# Sensor_HallArray_StandAlone_5mm.net
KiCad netlist of a schematic drawn in EAGLE
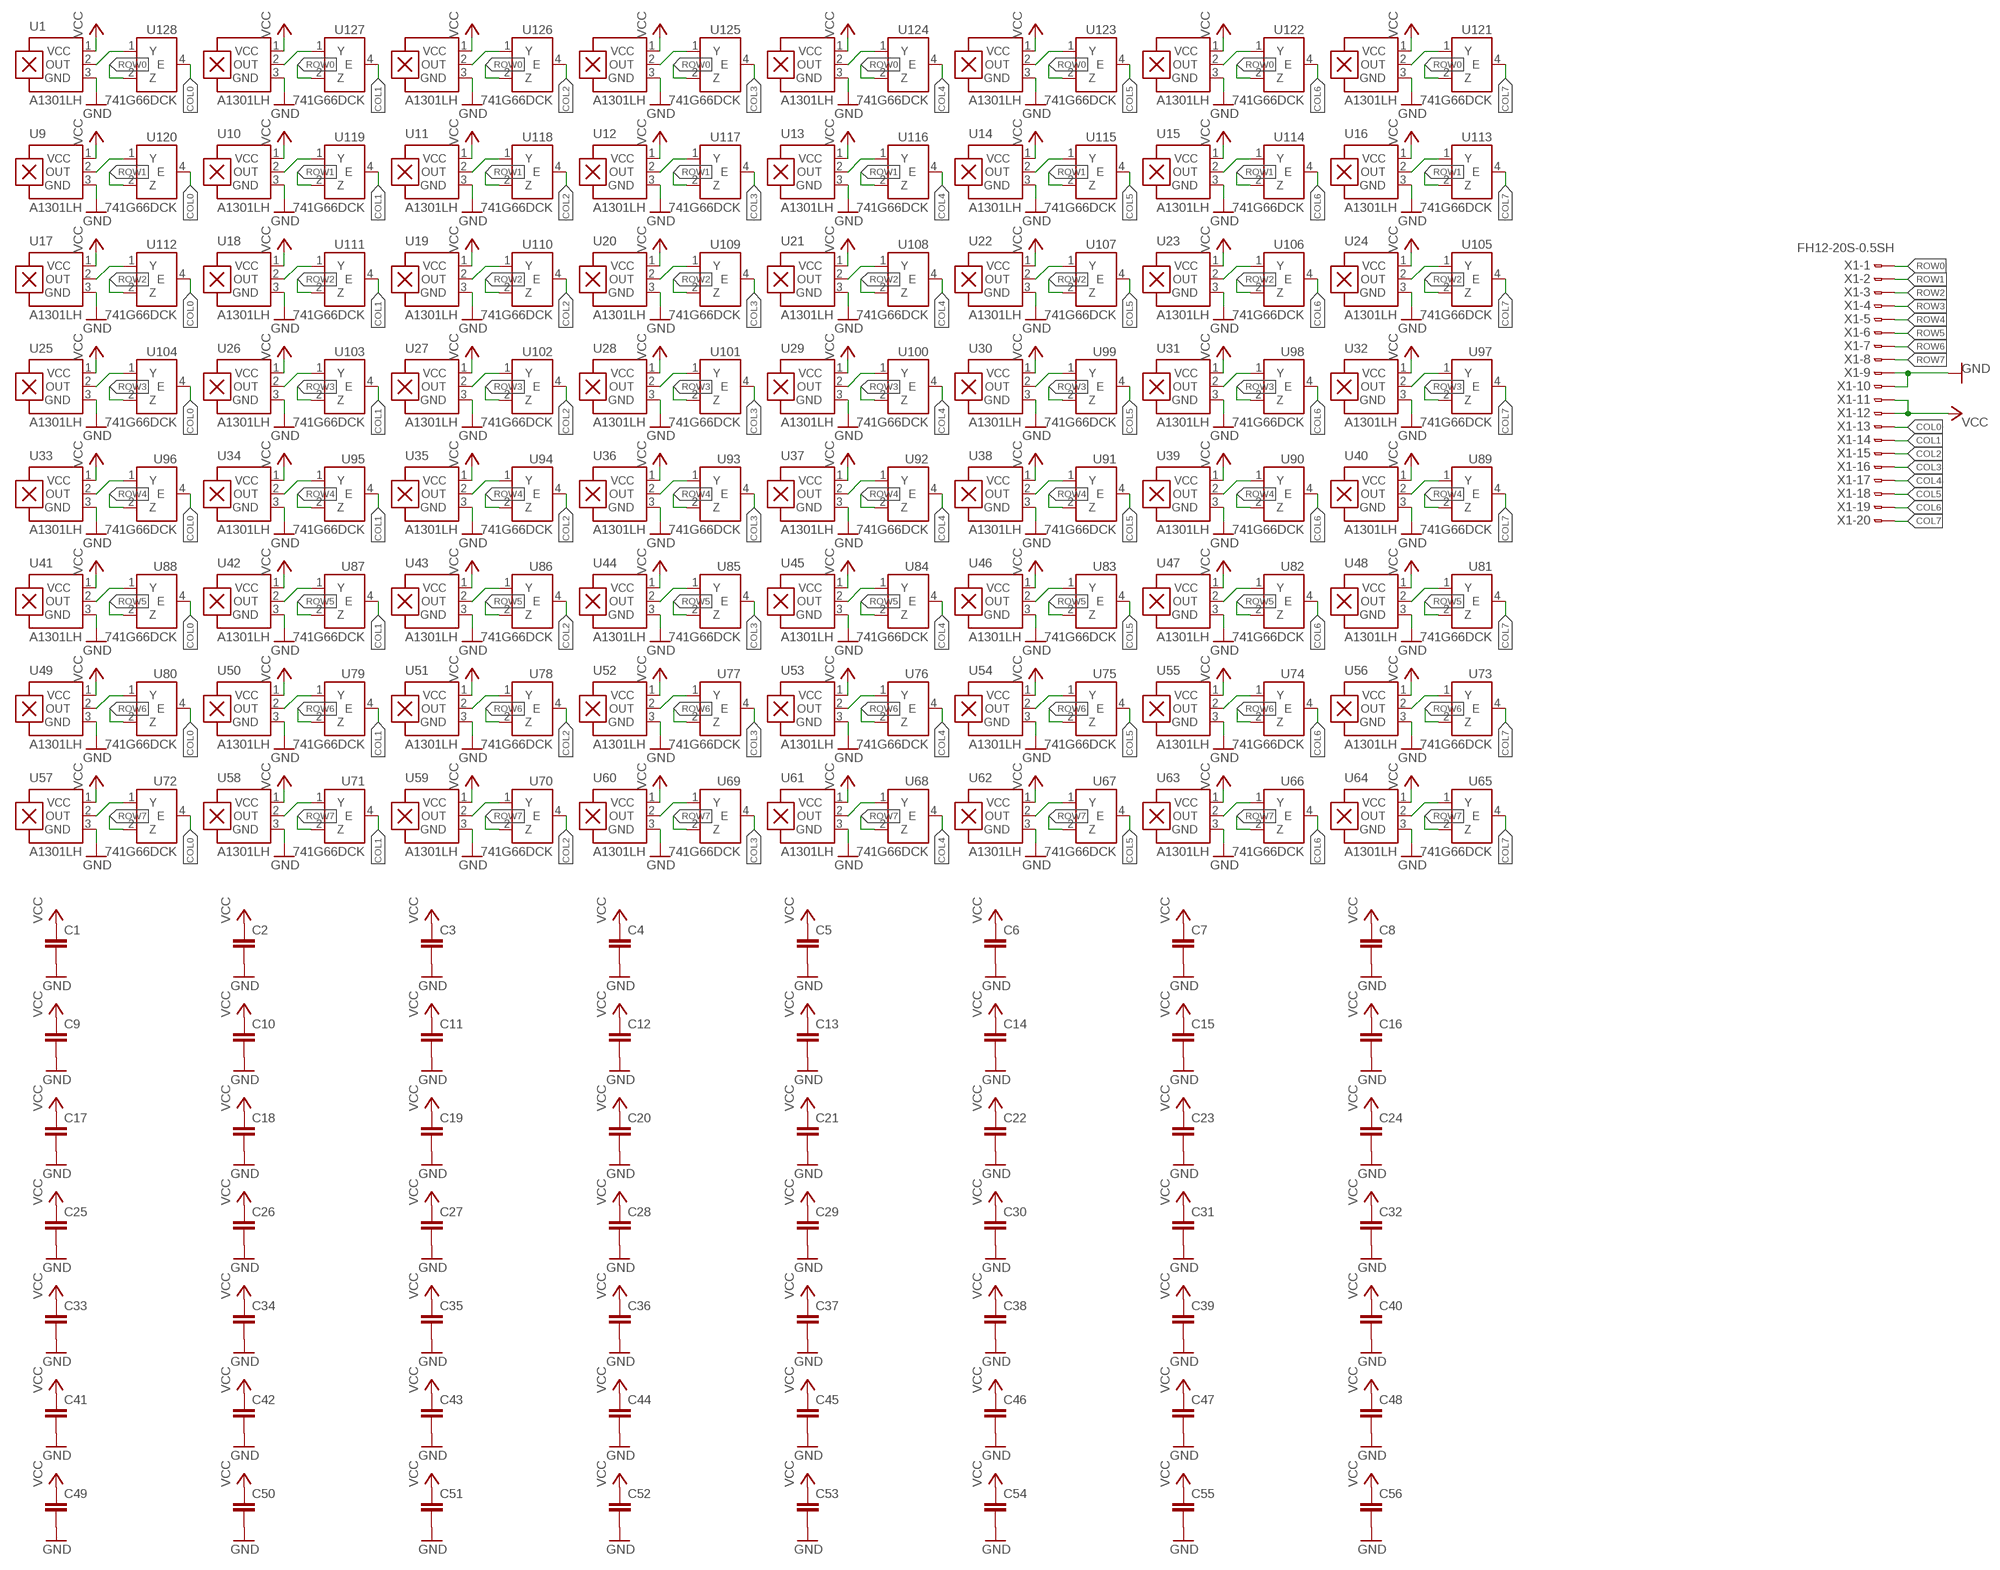
[diagram p0: schematic, sheet 1]

(export (version "E")
  (design (tool "Eeschema 10.0.6"))
  (components
    (comp (ref "C1")
      (value "C-EUC0402")
      (footprint "eagle-import:C0402")
      (libsource (lib "eagle-import") (part "C-EUC0402"))
    )
    (comp (ref "C2")
      (value "C-EUC0402")
      (footprint "eagle-import:C0402")
      (libsource (lib "eagle-import") (part "C-EUC0402"))
    )
    (comp (ref "C3")
      (value "C-EUC0402")
      (footprint "eagle-import:C0402")
      (libsource (lib "eagle-import") (part "C-EUC0402"))
    )
    (comp (ref "C4")
      (value "C-EUC0402")
      (footprint "eagle-import:C0402")
      (libsource (lib "eagle-import") (part "C-EUC0402"))
    )
    (comp (ref "C5")
      (value "C-EUC0402")
      (footprint "eagle-import:C0402")
      (libsource (lib "eagle-import") (part "C-EUC0402"))
    )
    (comp (ref "C6")
      (value "C-EUC0402")
      (footprint "eagle-import:C0402")
      (libsource (lib "eagle-import") (part "C-EUC0402"))
    )
    (comp (ref "C7")
      (value "C-EUC0402")
      (footprint "eagle-import:C0402")
      (libsource (lib "eagle-import") (part "C-EUC0402"))
    )
    (comp (ref "C8")
      (value "C-EUC0402")
      (footprint "eagle-import:C0402")
      (libsource (lib "eagle-import") (part "C-EUC0402"))
    )
    (comp (ref "C9")
      (value "C-EUC0402")
      (footprint "eagle-import:C0402")
      (libsource (lib "eagle-import") (part "C-EUC0402"))
    )
    (comp (ref "C10")
      (value "C-EUC0402")
      (footprint "eagle-import:C0402")
      (libsource (lib "eagle-import") (part "C-EUC0402"))
    )
    (comp (ref "C11")
      (value "C-EUC0402")
      (footprint "eagle-import:C0402")
      (libsource (lib "eagle-import") (part "C-EUC0402"))
    )
    (comp (ref "C12")
      (value "C-EUC0402")
      (footprint "eagle-import:C0402")
      (libsource (lib "eagle-import") (part "C-EUC0402"))
    )
    (comp (ref "C13")
      (value "C-EUC0402")
      (footprint "eagle-import:C0402")
      (libsource (lib "eagle-import") (part "C-EUC0402"))
    )
    (comp (ref "C14")
      (value "C-EUC0402")
      (footprint "eagle-import:C0402")
      (libsource (lib "eagle-import") (part "C-EUC0402"))
    )
    (comp (ref "C15")
      (value "C-EUC0402")
      (footprint "eagle-import:C0402")
      (libsource (lib "eagle-import") (part "C-EUC0402"))
    )
    (comp (ref "C16")
      (value "C-EUC0402")
      (footprint "eagle-import:C0402")
      (libsource (lib "eagle-import") (part "C-EUC0402"))
    )
    (comp (ref "C17")
      (value "C-EUC0402")
      (footprint "eagle-import:C0402")
      (libsource (lib "eagle-import") (part "C-EUC0402"))
    )
    (comp (ref "C18")
      (value "C-EUC0402")
      (footprint "eagle-import:C0402")
      (libsource (lib "eagle-import") (part "C-EUC0402"))
    )
    (comp (ref "C19")
      (value "C-EUC0402")
      (footprint "eagle-import:C0402")
      (libsource (lib "eagle-import") (part "C-EUC0402"))
    )
    (comp (ref "C20")
      (value "C-EUC0402")
      (footprint "eagle-import:C0402")
      (libsource (lib "eagle-import") (part "C-EUC0402"))
    )
    (comp (ref "C21")
      (value "C-EUC0402")
      (footprint "eagle-import:C0402")
      (libsource (lib "eagle-import") (part "C-EUC0402"))
    )
    (comp (ref "C22")
      (value "C-EUC0402")
      (footprint "eagle-import:C0402")
      (libsource (lib "eagle-import") (part "C-EUC0402"))
    )
    (comp (ref "C23")
      (value "C-EUC0402")
      (footprint "eagle-import:C0402")
      (libsource (lib "eagle-import") (part "C-EUC0402"))
    )
    (comp (ref "C24")
      (value "C-EUC0402")
      (footprint "eagle-import:C0402")
      (libsource (lib "eagle-import") (part "C-EUC0402"))
    )
    (comp (ref "C25")
      (value "C-EUC0402")
      (footprint "eagle-import:C0402")
      (libsource (lib "eagle-import") (part "C-EUC0402"))
    )
    (comp (ref "C26")
      (value "C-EUC0402")
      (footprint "eagle-import:C0402")
      (libsource (lib "eagle-import") (part "C-EUC0402"))
    )
    (comp (ref "C27")
      (value "C-EUC0402")
      (footprint "eagle-import:C0402")
      (libsource (lib "eagle-import") (part "C-EUC0402"))
    )
    (comp (ref "C28")
      (value "C-EUC0402")
      (footprint "eagle-import:C0402")
      (libsource (lib "eagle-import") (part "C-EUC0402"))
    )
    (comp (ref "C29")
      (value "C-EUC0402")
      (footprint "eagle-import:C0402")
      (libsource (lib "eagle-import") (part "C-EUC0402"))
    )
    (comp (ref "C30")
      (value "C-EUC0402")
      (footprint "eagle-import:C0402")
      (libsource (lib "eagle-import") (part "C-EUC0402"))
    )
    (comp (ref "C31")
      (value "C-EUC0402")
      (footprint "eagle-import:C0402")
      (libsource (lib "eagle-import") (part "C-EUC0402"))
    )
    (comp (ref "C32")
      (value "C-EUC0402")
      (footprint "eagle-import:C0402")
      (libsource (lib "eagle-import") (part "C-EUC0402"))
    )
    (comp (ref "C33")
      (value "C-EUC0402")
      (footprint "eagle-import:C0402")
      (libsource (lib "eagle-import") (part "C-EUC0402"))
    )
    (comp (ref "C34")
      (value "C-EUC0402")
      (footprint "eagle-import:C0402")
      (libsource (lib "eagle-import") (part "C-EUC0402"))
    )
    (comp (ref "C35")
      (value "C-EUC0402")
      (footprint "eagle-import:C0402")
      (libsource (lib "eagle-import") (part "C-EUC0402"))
    )
    (comp (ref "C36")
      (value "C-EUC0402")
      (footprint "eagle-import:C0402")
      (libsource (lib "eagle-import") (part "C-EUC0402"))
    )
    (comp (ref "C37")
      (value "C-EUC0402")
      (footprint "eagle-import:C0402")
      (libsource (lib "eagle-import") (part "C-EUC0402"))
    )
    (comp (ref "C38")
      (value "C-EUC0402")
      (footprint "eagle-import:C0402")
      (libsource (lib "eagle-import") (part "C-EUC0402"))
    )
    (comp (ref "C39")
      (value "C-EUC0402")
      (footprint "eagle-import:C0402")
      (libsource (lib "eagle-import") (part "C-EUC0402"))
    )
    (comp (ref "C40")
      (value "C-EUC0402")
      (footprint "eagle-import:C0402")
      (libsource (lib "eagle-import") (part "C-EUC0402"))
    )
    (comp (ref "C41")
      (value "C-EUC0402")
      (footprint "eagle-import:C0402")
      (libsource (lib "eagle-import") (part "C-EUC0402"))
    )
    (comp (ref "C42")
      (value "C-EUC0402")
      (footprint "eagle-import:C0402")
      (libsource (lib "eagle-import") (part "C-EUC0402"))
    )
    (comp (ref "C43")
      (value "C-EUC0402")
      (footprint "eagle-import:C0402")
      (libsource (lib "eagle-import") (part "C-EUC0402"))
    )
    (comp (ref "C44")
      (value "C-EUC0402")
      (footprint "eagle-import:C0402")
      (libsource (lib "eagle-import") (part "C-EUC0402"))
    )
    (comp (ref "C45")
      (value "C-EUC0402")
      (footprint "eagle-import:C0402")
      (libsource (lib "eagle-import") (part "C-EUC0402"))
    )
    (comp (ref "C46")
      (value "C-EUC0402")
      (footprint "eagle-import:C0402")
      (libsource (lib "eagle-import") (part "C-EUC0402"))
    )
    (comp (ref "C47")
      (value "C-EUC0402")
      (footprint "eagle-import:C0402")
      (libsource (lib "eagle-import") (part "C-EUC0402"))
    )
    (comp (ref "C48")
      (value "C-EUC0402")
      (footprint "eagle-import:C0402")
      (libsource (lib "eagle-import") (part "C-EUC0402"))
    )
    (comp (ref "C49")
      (value "C-EUC0402")
      (footprint "eagle-import:C0402")
      (libsource (lib "eagle-import") (part "C-EUC0402"))
    )
    (comp (ref "C50")
      (value "C-EUC0402")
      (footprint "eagle-import:C0402")
      (libsource (lib "eagle-import") (part "C-EUC0402"))
    )
    (comp (ref "C51")
      (value "C-EUC0402")
      (footprint "eagle-import:C0402")
      (libsource (lib "eagle-import") (part "C-EUC0402"))
    )
    (comp (ref "C52")
      (value "C-EUC0402")
      (footprint "eagle-import:C0402")
      (libsource (lib "eagle-import") (part "C-EUC0402"))
    )
    (comp (ref "C53")
      (value "C-EUC0402")
      (footprint "eagle-import:C0402")
      (libsource (lib "eagle-import") (part "C-EUC0402"))
    )
    (comp (ref "C54")
      (value "C-EUC0402")
      (footprint "eagle-import:C0402")
      (libsource (lib "eagle-import") (part "C-EUC0402"))
    )
    (comp (ref "C55")
      (value "C-EUC0402")
      (footprint "eagle-import:C0402")
      (libsource (lib "eagle-import") (part "C-EUC0402"))
    )
    (comp (ref "C56")
      (value "C-EUC0402")
      (footprint "eagle-import:C0402")
      (libsource (lib "eagle-import") (part "C-EUC0402"))
    )
    (comp (ref "U1")
      (value "A1301LH")
      (footprint "eagle-import:SOT23-W")
      (fields (field (name "MF") "ALLEGRO MICROSYSTEMS, INC.") (field (name "MPN") "A1301ELHLT-T"))
      (libsource (lib "eagle-import") (part "A13?LH01"))
    )
    (comp (ref "U2")
      (value "A1301LH")
      (footprint "eagle-import:SOT23-W")
      (fields (field (name "MF") "ALLEGRO MICROSYSTEMS, INC.") (field (name "MPN") "A1301ELHLT-T"))
      (libsource (lib "eagle-import") (part "A13?LH01"))
    )
    (comp (ref "U3")
      (value "A1301LH")
      (footprint "eagle-import:SOT23-W")
      (fields (field (name "MF") "ALLEGRO MICROSYSTEMS, INC.") (field (name "MPN") "A1301ELHLT-T"))
      (libsource (lib "eagle-import") (part "A13?LH01"))
    )
    (comp (ref "U4")
      (value "A1301LH")
      (footprint "eagle-import:SOT23-W")
      (fields (field (name "MF") "ALLEGRO MICROSYSTEMS, INC.") (field (name "MPN") "A1301ELHLT-T"))
      (libsource (lib "eagle-import") (part "A13?LH01"))
    )
    (comp (ref "U5")
      (value "A1301LH")
      (footprint "eagle-import:SOT23-W")
      (fields (field (name "MF") "ALLEGRO MICROSYSTEMS, INC.") (field (name "MPN") "A1301ELHLT-T"))
      (libsource (lib "eagle-import") (part "A13?LH01"))
    )
    (comp (ref "U6")
      (value "A1301LH")
      (footprint "eagle-import:SOT23-W")
      (fields (field (name "MF") "ALLEGRO MICROSYSTEMS, INC.") (field (name "MPN") "A1301ELHLT-T"))
      (libsource (lib "eagle-import") (part "A13?LH01"))
    )
    (comp (ref "U7")
      (value "A1301LH")
      (footprint "eagle-import:SOT23-W")
      (fields (field (name "MF") "ALLEGRO MICROSYSTEMS, INC.") (field (name "MPN") "A1301ELHLT-T"))
      (libsource (lib "eagle-import") (part "A13?LH01"))
    )
    (comp (ref "U8")
      (value "A1301LH")
      (footprint "eagle-import:SOT23-W")
      (fields (field (name "MF") "ALLEGRO MICROSYSTEMS, INC.") (field (name "MPN") "A1301ELHLT-T"))
      (libsource (lib "eagle-import") (part "A13?LH01"))
    )
    (comp (ref "U9")
      (value "A1301LH")
      (footprint "eagle-import:SOT23-W")
      (fields (field (name "MF") "ALLEGRO MICROSYSTEMS, INC.") (field (name "MPN") "A1301ELHLT-T"))
      (libsource (lib "eagle-import") (part "A13?LH01"))
    )
    (comp (ref "U10")
      (value "A1301LH")
      (footprint "eagle-import:SOT23-W")
      (fields (field (name "MF") "ALLEGRO MICROSYSTEMS, INC.") (field (name "MPN") "A1301ELHLT-T"))
      (libsource (lib "eagle-import") (part "A13?LH01"))
    )
    (comp (ref "U11")
      (value "A1301LH")
      (footprint "eagle-import:SOT23-W")
      (fields (field (name "MF") "ALLEGRO MICROSYSTEMS, INC.") (field (name "MPN") "A1301ELHLT-T"))
      (libsource (lib "eagle-import") (part "A13?LH01"))
    )
    (comp (ref "U12")
      (value "A1301LH")
      (footprint "eagle-import:SOT23-W")
      (fields (field (name "MF") "ALLEGRO MICROSYSTEMS, INC.") (field (name "MPN") "A1301ELHLT-T"))
      (libsource (lib "eagle-import") (part "A13?LH01"))
    )
    (comp (ref "U13")
      (value "A1301LH")
      (footprint "eagle-import:SOT23-W")
      (fields (field (name "MF") "ALLEGRO MICROSYSTEMS, INC.") (field (name "MPN") "A1301ELHLT-T"))
      (libsource (lib "eagle-import") (part "A13?LH01"))
    )
    (comp (ref "U14")
      (value "A1301LH")
      (footprint "eagle-import:SOT23-W")
      (fields (field (name "MF") "ALLEGRO MICROSYSTEMS, INC.") (field (name "MPN") "A1301ELHLT-T"))
      (libsource (lib "eagle-import") (part "A13?LH01"))
    )
    (comp (ref "U15")
      (value "A1301LH")
      (footprint "eagle-import:SOT23-W")
      (fields (field (name "MF") "ALLEGRO MICROSYSTEMS, INC.") (field (name "MPN") "A1301ELHLT-T"))
      (libsource (lib "eagle-import") (part "A13?LH01"))
    )
    (comp (ref "U16")
      (value "A1301LH")
      (footprint "eagle-import:SOT23-W")
      (fields (field (name "MF") "ALLEGRO MICROSYSTEMS, INC.") (field (name "MPN") "A1301ELHLT-T"))
      (libsource (lib "eagle-import") (part "A13?LH01"))
    )
    (comp (ref "U17")
      (value "A1301LH")
      (footprint "eagle-import:SOT23-W")
      (fields (field (name "MF") "ALLEGRO MICROSYSTEMS, INC.") (field (name "MPN") "A1301ELHLT-T"))
      (libsource (lib "eagle-import") (part "A13?LH01"))
    )
    (comp (ref "U18")
      (value "A1301LH")
      (footprint "eagle-import:SOT23-W")
      (fields (field (name "MF") "ALLEGRO MICROSYSTEMS, INC.") (field (name "MPN") "A1301ELHLT-T"))
      (libsource (lib "eagle-import") (part "A13?LH01"))
    )
    (comp (ref "U19")
      (value "A1301LH")
      (footprint "eagle-import:SOT23-W")
      (fields (field (name "MF") "ALLEGRO MICROSYSTEMS, INC.") (field (name "MPN") "A1301ELHLT-T"))
      (libsource (lib "eagle-import") (part "A13?LH01"))
    )
    (comp (ref "U20")
      (value "A1301LH")
      (footprint "eagle-import:SOT23-W")
      (fields (field (name "MF") "ALLEGRO MICROSYSTEMS, INC.") (field (name "MPN") "A1301ELHLT-T"))
      (libsource (lib "eagle-import") (part "A13?LH01"))
    )
    (comp (ref "U21")
      (value "A1301LH")
      (footprint "eagle-import:SOT23-W")
      (fields (field (name "MF") "ALLEGRO MICROSYSTEMS, INC.") (field (name "MPN") "A1301ELHLT-T"))
      (libsource (lib "eagle-import") (part "A13?LH01"))
    )
    (comp (ref "U22")
      (value "A1301LH")
      (footprint "eagle-import:SOT23-W")
      (fields (field (name "MF") "ALLEGRO MICROSYSTEMS, INC.") (field (name "MPN") "A1301ELHLT-T"))
      (libsource (lib "eagle-import") (part "A13?LH01"))
    )
    (comp (ref "U23")
      (value "A1301LH")
      (footprint "eagle-import:SOT23-W")
      (fields (field (name "MF") "ALLEGRO MICROSYSTEMS, INC.") (field (name "MPN") "A1301ELHLT-T"))
      (libsource (lib "eagle-import") (part "A13?LH01"))
    )
    (comp (ref "U24")
      (value "A1301LH")
      (footprint "eagle-import:SOT23-W")
      (fields (field (name "MF") "ALLEGRO MICROSYSTEMS, INC.") (field (name "MPN") "A1301ELHLT-T"))
      (libsource (lib "eagle-import") (part "A13?LH01"))
    )
    (comp (ref "U25")
      (value "A1301LH")
      (footprint "eagle-import:SOT23-W")
      (fields (field (name "MF") "ALLEGRO MICROSYSTEMS, INC.") (field (name "MPN") "A1301ELHLT-T"))
      (libsource (lib "eagle-import") (part "A13?LH01"))
    )
    (comp (ref "U26")
      (value "A1301LH")
      (footprint "eagle-import:SOT23-W")
      (fields (field (name "MF") "ALLEGRO MICROSYSTEMS, INC.") (field (name "MPN") "A1301ELHLT-T"))
      (libsource (lib "eagle-import") (part "A13?LH01"))
    )
    (comp (ref "U27")
      (value "A1301LH")
      (footprint "eagle-import:SOT23-W")
      (fields (field (name "MF") "ALLEGRO MICROSYSTEMS, INC.") (field (name "MPN") "A1301ELHLT-T"))
      (libsource (lib "eagle-import") (part "A13?LH01"))
    )
    (comp (ref "U28")
      (value "A1301LH")
      (footprint "eagle-import:SOT23-W")
      (fields (field (name "MF") "ALLEGRO MICROSYSTEMS, INC.") (field (name "MPN") "A1301ELHLT-T"))
      (libsource (lib "eagle-import") (part "A13?LH01"))
    )
    (comp (ref "U29")
      (value "A1301LH")
      (footprint "eagle-import:SOT23-W")
      (fields (field (name "MF") "ALLEGRO MICROSYSTEMS, INC.") (field (name "MPN") "A1301ELHLT-T"))
      (libsource (lib "eagle-import") (part "A13?LH01"))
    )
    (comp (ref "U30")
      (value "A1301LH")
      (footprint "eagle-import:SOT23-W")
      (fields (field (name "MF") "ALLEGRO MICROSYSTEMS, INC.") (field (name "MPN") "A1301ELHLT-T"))
      (libsource (lib "eagle-import") (part "A13?LH01"))
    )
    (comp (ref "U31")
      (value "A1301LH")
      (footprint "eagle-import:SOT23-W")
      (fields (field (name "MF") "ALLEGRO MICROSYSTEMS, INC.") (field (name "MPN") "A1301ELHLT-T"))
      (libsource (lib "eagle-import") (part "A13?LH01"))
    )
    (comp (ref "U32")
      (value "A1301LH")
      (footprint "eagle-import:SOT23-W")
      (fields (field (name "MF") "ALLEGRO MICROSYSTEMS, INC.") (field (name "MPN") "A1301ELHLT-T"))
      (libsource (lib "eagle-import") (part "A13?LH01"))
    )
    (comp (ref "U33")
      (value "A1301LH")
      (footprint "eagle-import:SOT23-W")
      (fields (field (name "MF") "ALLEGRO MICROSYSTEMS, INC.") (field (name "MPN") "A1301ELHLT-T"))
      (libsource (lib "eagle-import") (part "A13?LH01"))
    )
    (comp (ref "U34")
      (value "A1301LH")
      (footprint "eagle-import:SOT23-W")
      (fields (field (name "MF") "ALLEGRO MICROSYSTEMS, INC.") (field (name "MPN") "A1301ELHLT-T"))
      (libsource (lib "eagle-import") (part "A13?LH01"))
    )
    (comp (ref "U35")
      (value "A1301LH")
      (footprint "eagle-import:SOT23-W")
      (fields (field (name "MF") "ALLEGRO MICROSYSTEMS, INC.") (field (name "MPN") "A1301ELHLT-T"))
      (libsource (lib "eagle-import") (part "A13?LH01"))
    )
    (comp (ref "U36")
      (value "A1301LH")
      (footprint "eagle-import:SOT23-W")
      (fields (field (name "MF") "ALLEGRO MICROSYSTEMS, INC.") (field (name "MPN") "A1301ELHLT-T"))
      (libsource (lib "eagle-import") (part "A13?LH01"))
    )
    (comp (ref "U37")
      (value "A1301LH")
      (footprint "eagle-import:SOT23-W")
      (fields (field (name "MF") "ALLEGRO MICROSYSTEMS, INC.") (field (name "MPN") "A1301ELHLT-T"))
      (libsource (lib "eagle-import") (part "A13?LH01"))
    )
    (comp (ref "U38")
      (value "A1301LH")
      (footprint "eagle-import:SOT23-W")
      (fields (field (name "MF") "ALLEGRO MICROSYSTEMS, INC.") (field (name "MPN") "A1301ELHLT-T"))
      (libsource (lib "eagle-import") (part "A13?LH01"))
    )
    (comp (ref "U39")
      (value "A1301LH")
      (footprint "eagle-import:SOT23-W")
      (fields (field (name "MF") "ALLEGRO MICROSYSTEMS, INC.") (field (name "MPN") "A1301ELHLT-T"))
      (libsource (lib "eagle-import") (part "A13?LH01"))
    )
    (comp (ref "U40")
      (value "A1301LH")
      (footprint "eagle-import:SOT23-W")
      (fields (field (name "MF") "ALLEGRO MICROSYSTEMS, INC.") (field (name "MPN") "A1301ELHLT-T"))
      (libsource (lib "eagle-import") (part "A13?LH01"))
    )
    (comp (ref "U41")
      (value "A1301LH")
      (footprint "eagle-import:SOT23-W")
      (fields (field (name "MF") "ALLEGRO MICROSYSTEMS, INC.") (field (name "MPN") "A1301ELHLT-T"))
      (libsource (lib "eagle-import") (part "A13?LH01"))
    )
    (comp (ref "U42")
      (value "A1301LH")
      (footprint "eagle-import:SOT23-W")
      (fields (field (name "MF") "ALLEGRO MICROSYSTEMS, INC.") (field (name "MPN") "A1301ELHLT-T"))
      (libsource (lib "eagle-import") (part "A13?LH01"))
    )
    (comp (ref "U43")
      (value "A1301LH")
      (footprint "eagle-import:SOT23-W")
      (fields (field (name "MF") "ALLEGRO MICROSYSTEMS, INC.") (field (name "MPN") "A1301ELHLT-T"))
      (libsource (lib "eagle-import") (part "A13?LH01"))
    )
    (comp (ref "U44")
      (value "A1301LH")
      (footprint "eagle-import:SOT23-W")
      (fields (field (name "MF") "ALLEGRO MICROSYSTEMS, INC.") (field (name "MPN") "A1301ELHLT-T"))
      (libsource (lib "eagle-import") (part "A13?LH01"))
    )
    (comp (ref "U45")
      (value "A1301LH")
      (footprint "eagle-import:SOT23-W")
      (fields (field (name "MF") "ALLEGRO MICROSYSTEMS, INC.") (field (name "MPN") "A1301ELHLT-T"))
      (libsource (lib "eagle-import") (part "A13?LH01"))
    )
    (comp (ref "U46")
      (value "A1301LH")
      (footprint "eagle-import:SOT23-W")
      (fields (field (name "MF") "ALLEGRO MICROSYSTEMS, INC.") (field (name "MPN") "A1301ELHLT-T"))
      (libsource (lib "eagle-import") (part "A13?LH01"))
    )
    (comp (ref "U47")
      (value "A1301LH")
      (footprint "eagle-import:SOT23-W")
      (fields (field (name "MF") "ALLEGRO MICROSYSTEMS, INC.") (field (name "MPN") "A1301ELHLT-T"))
      (libsource (lib "eagle-import") (part "A13?LH01"))
    )
    (comp (ref "U48")
      (value "A1301LH")
      (footprint "eagle-import:SOT23-W")
      (fields (field (name "MF") "ALLEGRO MICROSYSTEMS, INC.") (field (name "MPN") "A1301ELHLT-T"))
      (libsource (lib "eagle-import") (part "A13?LH01"))
    )
    (comp (ref "U49")
      (value "A1301LH")
      (footprint "eagle-import:SOT23-W")
      (fields (field (name "MF") "ALLEGRO MICROSYSTEMS, INC.") (field (name "MPN") "A1301ELHLT-T"))
      (libsource (lib "eagle-import") (part "A13?LH01"))
    )
    (comp (ref "U50")
      (value "A1301LH")
      (footprint "eagle-import:SOT23-W")
      (fields (field (name "MF") "ALLEGRO MICROSYSTEMS, INC.") (field (name "MPN") "A1301ELHLT-T"))
      (libsource (lib "eagle-import") (part "A13?LH01"))
    )
    (comp (ref "U51")
      (value "A1301LH")
      (footprint "eagle-import:SOT23-W")
      (fields (field (name "MF") "ALLEGRO MICROSYSTEMS, INC.") (field (name "MPN") "A1301ELHLT-T"))
      (libsource (lib "eagle-import") (part "A13?LH01"))
    )
    (comp (ref "U52")
      (value "A1301LH")
      (footprint "eagle-import:SOT23-W")
      (fields (field (name "MF") "ALLEGRO MICROSYSTEMS, INC.") (field (name "MPN") "A1301ELHLT-T"))
      (libsource (lib "eagle-import") (part "A13?LH01"))
    )
    (comp (ref "U53")
      (value "A1301LH")
      (footprint "eagle-import:SOT23-W")
      (fields (field (name "MF") "ALLEGRO MICROSYSTEMS, INC.") (field (name "MPN") "A1301ELHLT-T"))
      (libsource (lib "eagle-import") (part "A13?LH01"))
    )
    (comp (ref "U54")
      (value "A1301LH")
      (footprint "eagle-import:SOT23-W")
      (fields (field (name "MF") "ALLEGRO MICROSYSTEMS, INC.") (field (name "MPN") "A1301ELHLT-T"))
      (libsource (lib "eagle-import") (part "A13?LH01"))
    )
    (comp (ref "U55")
      (value "A1301LH")
      (footprint "eagle-import:SOT23-W")
      (fields (field (name "MF") "ALLEGRO MICROSYSTEMS, INC.") (field (name "MPN") "A1301ELHLT-T"))
      (libsource (lib "eagle-import") (part "A13?LH01"))
    )
    (comp (ref "U56")
      (value "A1301LH")
      (footprint "eagle-import:SOT23-W")
      (fields (field (name "MF") "ALLEGRO MICROSYSTEMS, INC.") (field (name "MPN") "A1301ELHLT-T"))
      (libsource (lib "eagle-import") (part "A13?LH01"))
    )
    (comp (ref "U57")
      (value "A1301LH")
      (footprint "eagle-import:SOT23-W")
      (fields (field (name "MF") "ALLEGRO MICROSYSTEMS, INC.") (field (name "MPN") "A1301ELHLT-T"))
      (libsource (lib "eagle-import") (part "A13?LH01"))
    )
    (comp (ref "U58")
      (value "A1301LH")
      (footprint "eagle-import:SOT23-W")
      (fields (field (name "MF") "ALLEGRO MICROSYSTEMS, INC.") (field (name "MPN") "A1301ELHLT-T"))
      (libsource (lib "eagle-import") (part "A13?LH01"))
    )
    (comp (ref "U59")
      (value "A1301LH")
      (footprint "eagle-import:SOT23-W")
      (fields (field (name "MF") "ALLEGRO MICROSYSTEMS, INC.") (field (name "MPN") "A1301ELHLT-T"))
      (libsource (lib "eagle-import") (part "A13?LH01"))
    )
    (comp (ref "U60")
      (value "A1301LH")
      (footprint "eagle-import:SOT23-W")
      (fields (field (name "MF") "ALLEGRO MICROSYSTEMS, INC.") (field (name "MPN") "A1301ELHLT-T"))
      (libsource (lib "eagle-import") (part "A13?LH01"))
    )
    (comp (ref "U61")
      (value "A1301LH")
      (footprint "eagle-import:SOT23-W")
      (fields (field (name "MF") "ALLEGRO MICROSYSTEMS, INC.") (field (name "MPN") "A1301ELHLT-T"))
      (libsource (lib "eagle-import") (part "A13?LH01"))
    )
    (comp (ref "U62")
      (value "A1301LH")
      (footprint "eagle-import:SOT23-W")
      (fields (field (name "MF") "ALLEGRO MICROSYSTEMS, INC.") (field (name "MPN") "A1301ELHLT-T"))
      (libsource (lib "eagle-import") (part "A13?LH01"))
    )
    (comp (ref "U63")
      (value "A1301LH")
      (footprint "eagle-import:SOT23-W")
      (fields (field (name "MF") "ALLEGRO MICROSYSTEMS, INC.") (field (name "MPN") "A1301ELHLT-T"))
      (libsource (lib "eagle-import") (part "A13?LH01"))
    )
    (comp (ref "U64")
      (value "A1301LH")
      (footprint "eagle-import:SOT23-W")
      (fields (field (name "MF") "ALLEGRO MICROSYSTEMS, INC.") (field (name "MPN") "A1301ELHLT-T"))
      (libsource (lib "eagle-import") (part "A13?LH01"))
    )
    (comp (ref "U65")
      (value "741G66DCK")
      (footprint "eagle-import:SC70-5")
      (libsource (lib "eagle-import") (part "741G66DCK"))
    )
    (comp (ref "U66")
      (value "741G66DCK")
      (footprint "eagle-import:SC70-5")
      (libsource (lib "eagle-import") (part "741G66DCK"))
    )
    (comp (ref "U67")
      (value "741G66DCK")
      (footprint "eagle-import:SC70-5")
      (libsource (lib "eagle-import") (part "741G66DCK"))
    )
    (comp (ref "U68")
      (value "741G66DCK")
      (footprint "eagle-import:SC70-5")
      (libsource (lib "eagle-import") (part "741G66DCK"))
    )
    (comp (ref "U69")
      (value "741G66DCK")
      (footprint "eagle-import:SC70-5")
      (libsource (lib "eagle-import") (part "741G66DCK"))
    )
    (comp (ref "U70")
      (value "741G66DCK")
      (footprint "eagle-import:SC70-5")
      (libsource (lib "eagle-import") (part "741G66DCK"))
    )
    (comp (ref "U71")
      (value "741G66DCK")
      (footprint "eagle-import:SC70-5")
      (libsource (lib "eagle-import") (part "741G66DCK"))
    )
    (comp (ref "U72")
      (value "741G66DCK")
      (footprint "eagle-import:SC70-5")
      (libsource (lib "eagle-import") (part "741G66DCK"))
    )
    (comp (ref "U73")
      (value "741G66DCK")
      (footprint "eagle-import:SC70-5")
      (libsource (lib "eagle-import") (part "741G66DCK"))
    )
    (comp (ref "U74")
      (value "741G66DCK")
      (footprint "eagle-import:SC70-5")
      (libsource (lib "eagle-import") (part "741G66DCK"))
    )
    (comp (ref "U75")
      (value "741G66DCK")
      (footprint "eagle-import:SC70-5")
      (libsource (lib "eagle-import") (part "741G66DCK"))
    )
    (comp (ref "U76")
      (value "741G66DCK")
      (footprint "eagle-import:SC70-5")
      (libsource (lib "eagle-import") (part "741G66DCK"))
    )
    (comp (ref "U77")
      (value "741G66DCK")
      (footprint "eagle-import:SC70-5")
      (libsource (lib "eagle-import") (part "741G66DCK"))
    )
    (comp (ref "U78")
      (value "741G66DCK")
      (footprint "eagle-import:SC70-5")
      (libsource (lib "eagle-import") (part "741G66DCK"))
    )
    (comp (ref "U79")
      (value "741G66DCK")
      (footprint "eagle-import:SC70-5")
      (libsource (lib "eagle-import") (part "741G66DCK"))
    )
    (comp (ref "U80")
      (value "741G66DCK")
      (footprint "eagle-import:SC70-5")
      (libsource (lib "eagle-import") (part "741G66DCK"))
    )
    (comp (ref "U81")
      (value "741G66DCK")
      (footprint "eagle-import:SC70-5")
      (libsource (lib "eagle-import") (part "741G66DCK"))
    )
    (comp (ref "U82")
      (value "741G66DCK")
      (footprint "eagle-import:SC70-5")
      (libsource (lib "eagle-import") (part "741G66DCK"))
    )
    (comp (ref "U83")
      (value "741G66DCK")
      (footprint "eagle-import:SC70-5")
      (libsource (lib "eagle-import") (part "741G66DCK"))
    )
    (comp (ref "U84")
      (value "741G66DCK")
      (footprint "eagle-import:SC70-5")
      (libsource (lib "eagle-import") (part "741G66DCK"))
    )
    (comp (ref "U85")
      (value "741G66DCK")
      (footprint "eagle-import:SC70-5")
      (libsource (lib "eagle-import") (part "741G66DCK"))
    )
    (comp (ref "U86")
      (value "741G66DCK")
      (footprint "eagle-import:SC70-5")
      (libsource (lib "eagle-import") (part "741G66DCK"))
    )
    (comp (ref "U87")
      (value "741G66DCK")
      (footprint "eagle-import:SC70-5")
      (libsource (lib "eagle-import") (part "741G66DCK"))
    )
    (comp (ref "U88")
      (value "741G66DCK")
      (footprint "eagle-import:SC70-5")
      (libsource (lib "eagle-import") (part "741G66DCK"))
    )
    (comp (ref "U89")
      (value "741G66DCK")
      (footprint "eagle-import:SC70-5")
      (libsource (lib "eagle-import") (part "741G66DCK"))
    )
    (comp (ref "U90")
      (value "741G66DCK")
      (footprint "eagle-import:SC70-5")
      (libsource (lib "eagle-import") (part "741G66DCK"))
    )
    (comp (ref "U91")
      (value "741G66DCK")
      (footprint "eagle-import:SC70-5")
      (libsource (lib "eagle-import") (part "741G66DCK"))
    )
    (comp (ref "U92")
      (value "741G66DCK")
      (footprint "eagle-import:SC70-5")
      (libsource (lib "eagle-import") (part "741G66DCK"))
    )
    (comp (ref "U93")
      (value "741G66DCK")
      (footprint "eagle-import:SC70-5")
      (libsource (lib "eagle-import") (part "741G66DCK"))
    )
    (comp (ref "U94")
      (value "741G66DCK")
      (footprint "eagle-import:SC70-5")
      (libsource (lib "eagle-import") (part "741G66DCK"))
    )
    (comp (ref "U95")
      (value "741G66DCK")
      (footprint "eagle-import:SC70-5")
      (libsource (lib "eagle-import") (part "741G66DCK"))
    )
    (comp (ref "U96")
      (value "741G66DCK")
      (footprint "eagle-import:SC70-5")
      (libsource (lib "eagle-import") (part "741G66DCK"))
    )
    (comp (ref "U97")
      (value "741G66DCK")
      (footprint "eagle-import:SC70-5")
      (libsource (lib "eagle-import") (part "741G66DCK"))
    )
    (comp (ref "U98")
      (value "741G66DCK")
      (footprint "eagle-import:SC70-5")
      (libsource (lib "eagle-import") (part "741G66DCK"))
    )
    (comp (ref "U99")
      (value "741G66DCK")
      (footprint "eagle-import:SC70-5")
      (libsource (lib "eagle-import") (part "741G66DCK"))
    )
    (comp (ref "U100")
      (value "741G66DCK")
      (footprint "eagle-import:SC70-5")
      (libsource (lib "eagle-import") (part "741G66DCK"))
    )
    (comp (ref "U101")
      (value "741G66DCK")
      (footprint "eagle-import:SC70-5")
      (libsource (lib "eagle-import") (part "741G66DCK"))
    )
    (comp (ref "U102")
      (value "741G66DCK")
      (footprint "eagle-import:SC70-5")
      (libsource (lib "eagle-import") (part "741G66DCK"))
    )
    (comp (ref "U103")
      (value "741G66DCK")
      (footprint "eagle-import:SC70-5")
      (libsource (lib "eagle-import") (part "741G66DCK"))
    )
    (comp (ref "U104")
      (value "741G66DCK")
      (footprint "eagle-import:SC70-5")
      (libsource (lib "eagle-import") (part "741G66DCK"))
    )
    (comp (ref "U105")
      (value "741G66DCK")
      (footprint "eagle-import:SC70-5")
      (libsource (lib "eagle-import") (part "741G66DCK"))
    )
    (comp (ref "U106")
      (value "741G66DCK")
      (footprint "eagle-import:SC70-5")
      (libsource (lib "eagle-import") (part "741G66DCK"))
    )
    (comp (ref "U107")
      (value "741G66DCK")
      (footprint "eagle-import:SC70-5")
      (libsource (lib "eagle-import") (part "741G66DCK"))
    )
    (comp (ref "U108")
      (value "741G66DCK")
      (footprint "eagle-import:SC70-5")
      (libsource (lib "eagle-import") (part "741G66DCK"))
    )
    (comp (ref "U109")
      (value "741G66DCK")
      (footprint "eagle-import:SC70-5")
      (libsource (lib "eagle-import") (part "741G66DCK"))
    )
    (comp (ref "U110")
      (value "741G66DCK")
      (footprint "eagle-import:SC70-5")
      (libsource (lib "eagle-import") (part "741G66DCK"))
    )
    (comp (ref "U111")
      (value "741G66DCK")
      (footprint "eagle-import:SC70-5")
      (libsource (lib "eagle-import") (part "741G66DCK"))
    )
    (comp (ref "U112")
      (value "741G66DCK")
      (footprint "eagle-import:SC70-5")
      (libsource (lib "eagle-import") (part "741G66DCK"))
    )
    (comp (ref "U113")
      (value "741G66DCK")
      (footprint "eagle-import:SC70-5")
      (libsource (lib "eagle-import") (part "741G66DCK"))
    )
    (comp (ref "U114")
      (value "741G66DCK")
      (footprint "eagle-import:SC70-5")
      (libsource (lib "eagle-import") (part "741G66DCK"))
    )
    (comp (ref "U115")
      (value "741G66DCK")
      (footprint "eagle-import:SC70-5")
      (libsource (lib "eagle-import") (part "741G66DCK"))
    )
    (comp (ref "U116")
      (value "741G66DCK")
      (footprint "eagle-import:SC70-5")
      (libsource (lib "eagle-import") (part "741G66DCK"))
    )
    (comp (ref "U117")
      (value "741G66DCK")
      (footprint "eagle-import:SC70-5")
      (libsource (lib "eagle-import") (part "741G66DCK"))
    )
    (comp (ref "U118")
      (value "741G66DCK")
      (footprint "eagle-import:SC70-5")
      (libsource (lib "eagle-import") (part "741G66DCK"))
    )
    (comp (ref "U119")
      (value "741G66DCK")
      (footprint "eagle-import:SC70-5")
      (libsource (lib "eagle-import") (part "741G66DCK"))
    )
    (comp (ref "U120")
      (value "741G66DCK")
      (footprint "eagle-import:SC70-5")
      (libsource (lib "eagle-import") (part "741G66DCK"))
    )
    (comp (ref "U121")
      (value "741G66DCK")
      (footprint "eagle-import:SC70-5")
      (libsource (lib "eagle-import") (part "741G66DCK"))
    )
    (comp (ref "U122")
      (value "741G66DCK")
      (footprint "eagle-import:SC70-5")
      (libsource (lib "eagle-import") (part "741G66DCK"))
    )
    (comp (ref "U123")
      (value "741G66DCK")
      (footprint "eagle-import:SC70-5")
      (libsource (lib "eagle-import") (part "741G66DCK"))
    )
    (comp (ref "U124")
      (value "741G66DCK")
      (footprint "eagle-import:SC70-5")
      (libsource (lib "eagle-import") (part "741G66DCK"))
    )
    (comp (ref "U125")
      (value "741G66DCK")
      (footprint "eagle-import:SC70-5")
      (libsource (lib "eagle-import") (part "741G66DCK"))
    )
    (comp (ref "U126")
      (value "741G66DCK")
      (footprint "eagle-import:SC70-5")
      (libsource (lib "eagle-import") (part "741G66DCK"))
    )
    (comp (ref "U127")
      (value "741G66DCK")
      (footprint "eagle-import:SC70-5")
      (libsource (lib "eagle-import") (part "741G66DCK"))
    )
    (comp (ref "U128")
      (value "741G66DCK")
      (footprint "eagle-import:SC70-5")
      (libsource (lib "eagle-import") (part "741G66DCK"))
    )
    (comp (ref "X1")
      (value "FH12-20S-0.5SH")
      (footprint "eagle-import:FH12-20S-0.5SH")
      (fields (field (name "MPN") "FH12-20S-0.5SH(55)"))
      (libsource (lib "eagle-import") (part "FH12-20S-0.5SH"))
    )
  )
  (nets
    (net (code "1") (name "COL0") (class "Default")
      (node (ref "U104") (pin "4") (pinfunction "E_4") (pintype "input"))
      (node (ref "U112") (pin "4") (pinfunction "E_4") (pintype "input"))
      (node (ref "U120") (pin "4") (pinfunction "E_4") (pintype "input"))
      (node (ref "U128") (pin "4") (pinfunction "E_4") (pintype "input"))
      (node (ref "U72") (pin "4") (pinfunction "E_4") (pintype "input"))
      (node (ref "U80") (pin "4") (pinfunction "E_4") (pintype "input"))
      (node (ref "U88") (pin "4") (pinfunction "E_4") (pintype "input"))
      (node (ref "U96") (pin "4") (pinfunction "E_4") (pintype "input"))
      (node (ref "X1") (pin "13") (pinfunction "1_13") (pintype "passive"))
    )
    (net (code "2") (name "COL1") (class "Default")
      (node (ref "U103") (pin "4") (pinfunction "E_4") (pintype "input"))
      (node (ref "U111") (pin "4") (pinfunction "E_4") (pintype "input"))
      (node (ref "U119") (pin "4") (pinfunction "E_4") (pintype "input"))
      (node (ref "U127") (pin "4") (pinfunction "E_4") (pintype "input"))
      (node (ref "U71") (pin "4") (pinfunction "E_4") (pintype "input"))
      (node (ref "U79") (pin "4") (pinfunction "E_4") (pintype "input"))
      (node (ref "U87") (pin "4") (pinfunction "E_4") (pintype "input"))
      (node (ref "U95") (pin "4") (pinfunction "E_4") (pintype "input"))
      (node (ref "X1") (pin "14") (pinfunction "1_14") (pintype "passive"))
    )
    (net (code "3") (name "COL2") (class "Default")
      (node (ref "U102") (pin "4") (pinfunction "E_4") (pintype "input"))
      (node (ref "U110") (pin "4") (pinfunction "E_4") (pintype "input"))
      (node (ref "U118") (pin "4") (pinfunction "E_4") (pintype "input"))
      (node (ref "U126") (pin "4") (pinfunction "E_4") (pintype "input"))
      (node (ref "U70") (pin "4") (pinfunction "E_4") (pintype "input"))
      (node (ref "U78") (pin "4") (pinfunction "E_4") (pintype "input"))
      (node (ref "U86") (pin "4") (pinfunction "E_4") (pintype "input"))
      (node (ref "U94") (pin "4") (pinfunction "E_4") (pintype "input"))
      (node (ref "X1") (pin "15") (pinfunction "1_15") (pintype "passive"))
    )
    (net (code "4") (name "COL3") (class "Default")
      (node (ref "U101") (pin "4") (pinfunction "E_4") (pintype "input"))
      (node (ref "U109") (pin "4") (pinfunction "E_4") (pintype "input"))
      (node (ref "U117") (pin "4") (pinfunction "E_4") (pintype "input"))
      (node (ref "U125") (pin "4") (pinfunction "E_4") (pintype "input"))
      (node (ref "U69") (pin "4") (pinfunction "E_4") (pintype "input"))
      (node (ref "U77") (pin "4") (pinfunction "E_4") (pintype "input"))
      (node (ref "U85") (pin "4") (pinfunction "E_4") (pintype "input"))
      (node (ref "U93") (pin "4") (pinfunction "E_4") (pintype "input"))
      (node (ref "X1") (pin "16") (pinfunction "1_16") (pintype "passive"))
    )
    (net (code "5") (name "COL4") (class "Default")
      (node (ref "U100") (pin "4") (pinfunction "E_4") (pintype "input"))
      (node (ref "U108") (pin "4") (pinfunction "E_4") (pintype "input"))
      (node (ref "U116") (pin "4") (pinfunction "E_4") (pintype "input"))
      (node (ref "U124") (pin "4") (pinfunction "E_4") (pintype "input"))
      (node (ref "U68") (pin "4") (pinfunction "E_4") (pintype "input"))
      (node (ref "U76") (pin "4") (pinfunction "E_4") (pintype "input"))
      (node (ref "U84") (pin "4") (pinfunction "E_4") (pintype "input"))
      (node (ref "U92") (pin "4") (pinfunction "E_4") (pintype "input"))
      (node (ref "X1") (pin "17") (pinfunction "1_17") (pintype "passive"))
    )
    (net (code "6") (name "COL5") (class "Default")
      (node (ref "U107") (pin "4") (pinfunction "E_4") (pintype "input"))
      (node (ref "U115") (pin "4") (pinfunction "E_4") (pintype "input"))
      (node (ref "U123") (pin "4") (pinfunction "E_4") (pintype "input"))
      (node (ref "U67") (pin "4") (pinfunction "E_4") (pintype "input"))
      (node (ref "U75") (pin "4") (pinfunction "E_4") (pintype "input"))
      (node (ref "U83") (pin "4") (pinfunction "E_4") (pintype "input"))
      (node (ref "U91") (pin "4") (pinfunction "E_4") (pintype "input"))
      (node (ref "U99") (pin "4") (pinfunction "E_4") (pintype "input"))
      (node (ref "X1") (pin "18") (pinfunction "1_18") (pintype "passive"))
    )
    (net (code "7") (name "COL6") (class "Default")
      (node (ref "U106") (pin "4") (pinfunction "E_4") (pintype "input"))
      (node (ref "U114") (pin "4") (pinfunction "E_4") (pintype "input"))
      (node (ref "U122") (pin "4") (pinfunction "E_4") (pintype "input"))
      (node (ref "U66") (pin "4") (pinfunction "E_4") (pintype "input"))
      (node (ref "U74") (pin "4") (pinfunction "E_4") (pintype "input"))
      (node (ref "U82") (pin "4") (pinfunction "E_4") (pintype "input"))
      (node (ref "U90") (pin "4") (pinfunction "E_4") (pintype "input"))
      (node (ref "U98") (pin "4") (pinfunction "E_4") (pintype "input"))
      (node (ref "X1") (pin "19") (pinfunction "1_19") (pintype "passive"))
    )
    (net (code "8") (name "COL7") (class "Default")
      (node (ref "U105") (pin "4") (pinfunction "E_4") (pintype "input"))
      (node (ref "U113") (pin "4") (pinfunction "E_4") (pintype "input"))
      (node (ref "U121") (pin "4") (pinfunction "E_4") (pintype "input"))
      (node (ref "U65") (pin "4") (pinfunction "E_4") (pintype "input"))
      (node (ref "U73") (pin "4") (pinfunction "E_4") (pintype "input"))
      (node (ref "U81") (pin "4") (pinfunction "E_4") (pintype "input"))
      (node (ref "U89") (pin "4") (pinfunction "E_4") (pintype "input"))
      (node (ref "U97") (pin "4") (pinfunction "E_4") (pintype "input"))
      (node (ref "X1") (pin "20") (pinfunction "1_20") (pintype "passive"))
    )
    (net (code "9") (name "GND") (class "Default")
      (node (ref "C1") (pin "2") (pinfunction "2_2") (pintype "passive"))
      (node (ref "C10") (pin "2") (pinfunction "2_2") (pintype "passive"))
      (node (ref "C11") (pin "2") (pinfunction "2_2") (pintype "passive"))
      (node (ref "C12") (pin "2") (pinfunction "2_2") (pintype "passive"))
      (node (ref "C13") (pin "2") (pinfunction "2_2") (pintype "passive"))
      (node (ref "C14") (pin "2") (pinfunction "2_2") (pintype "passive"))
      (node (ref "C15") (pin "2") (pinfunction "2_2") (pintype "passive"))
      (node (ref "C16") (pin "2") (pinfunction "2_2") (pintype "passive"))
      (node (ref "C17") (pin "2") (pinfunction "2_2") (pintype "passive"))
      (node (ref "C18") (pin "2") (pinfunction "2_2") (pintype "passive"))
      (node (ref "C19") (pin "2") (pinfunction "2_2") (pintype "passive"))
      (node (ref "C2") (pin "2") (pinfunction "2_2") (pintype "passive"))
      (node (ref "C20") (pin "2") (pinfunction "2_2") (pintype "passive"))
      (node (ref "C21") (pin "2") (pinfunction "2_2") (pintype "passive"))
      (node (ref "C22") (pin "2") (pinfunction "2_2") (pintype "passive"))
      (node (ref "C23") (pin "2") (pinfunction "2_2") (pintype "passive"))
      (node (ref "C24") (pin "2") (pinfunction "2_2") (pintype "passive"))
      (node (ref "C25") (pin "2") (pinfunction "2_2") (pintype "passive"))
      (node (ref "C26") (pin "2") (pinfunction "2_2") (pintype "passive"))
      (node (ref "C27") (pin "2") (pinfunction "2_2") (pintype "passive"))
      (node (ref "C28") (pin "2") (pinfunction "2_2") (pintype "passive"))
      (node (ref "C29") (pin "2") (pinfunction "2_2") (pintype "passive"))
      (node (ref "C3") (pin "2") (pinfunction "2_2") (pintype "passive"))
      (node (ref "C30") (pin "2") (pinfunction "2_2") (pintype "passive"))
      (node (ref "C31") (pin "2") (pinfunction "2_2") (pintype "passive"))
      (node (ref "C32") (pin "2") (pinfunction "2_2") (pintype "passive"))
      (node (ref "C33") (pin "2") (pinfunction "2_2") (pintype "passive"))
      (node (ref "C34") (pin "2") (pinfunction "2_2") (pintype "passive"))
      (node (ref "C35") (pin "2") (pinfunction "2_2") (pintype "passive"))
      (node (ref "C36") (pin "2") (pinfunction "2_2") (pintype "passive"))
      (node (ref "C37") (pin "2") (pinfunction "2_2") (pintype "passive"))
      (node (ref "C38") (pin "2") (pinfunction "2_2") (pintype "passive"))
      (node (ref "C39") (pin "2") (pinfunction "2_2") (pintype "passive"))
      (node (ref "C4") (pin "2") (pinfunction "2_2") (pintype "passive"))
      (node (ref "C40") (pin "2") (pinfunction "2_2") (pintype "passive"))
      (node (ref "C41") (pin "2") (pinfunction "2_2") (pintype "passive"))
      (node (ref "C42") (pin "2") (pinfunction "2_2") (pintype "passive"))
      (node (ref "C43") (pin "2") (pinfunction "2_2") (pintype "passive"))
      (node (ref "C44") (pin "2") (pinfunction "2_2") (pintype "passive"))
      (node (ref "C45") (pin "2") (pinfunction "2_2") (pintype "passive"))
      (node (ref "C46") (pin "2") (pinfunction "2_2") (pintype "passive"))
      (node (ref "C47") (pin "2") (pinfunction "2_2") (pintype "passive"))
      (node (ref "C48") (pin "2") (pinfunction "2_2") (pintype "passive"))
      (node (ref "C49") (pin "2") (pinfunction "2_2") (pintype "passive"))
      (node (ref "C5") (pin "2") (pinfunction "2_2") (pintype "passive"))
      (node (ref "C50") (pin "2") (pinfunction "2_2") (pintype "passive"))
      (node (ref "C51") (pin "2") (pinfunction "2_2") (pintype "passive"))
      (node (ref "C52") (pin "2") (pinfunction "2_2") (pintype "passive"))
      (node (ref "C53") (pin "2") (pinfunction "2_2") (pintype "passive"))
      (node (ref "C54") (pin "2") (pinfunction "2_2") (pintype "passive"))
      (node (ref "C55") (pin "2") (pinfunction "2_2") (pintype "passive"))
      (node (ref "C56") (pin "2") (pinfunction "2_2") (pintype "passive"))
      (node (ref "C6") (pin "2") (pinfunction "2_2") (pintype "passive"))
      (node (ref "C7") (pin "2") (pinfunction "2_2") (pintype "passive"))
      (node (ref "C8") (pin "2") (pinfunction "2_2") (pintype "passive"))
      (node (ref "C9") (pin "2") (pinfunction "2_2") (pintype "passive"))
      (node (ref "U1") (pin "3") (pinfunction "GND_3") (pintype "power_in"))
      (node (ref "U10") (pin "3") (pinfunction "GND_3") (pintype "power_in"))
      (node (ref "U11") (pin "3") (pinfunction "GND_3") (pintype "power_in"))
      (node (ref "U12") (pin "3") (pinfunction "GND_3") (pintype "power_in"))
      (node (ref "U13") (pin "3") (pinfunction "GND_3") (pintype "power_in"))
      (node (ref "U14") (pin "3") (pinfunction "GND_3") (pintype "power_in"))
      (node (ref "U15") (pin "3") (pinfunction "GND_3") (pintype "power_in"))
      (node (ref "U16") (pin "3") (pinfunction "GND_3") (pintype "power_in"))
      (node (ref "U17") (pin "3") (pinfunction "GND_3") (pintype "power_in"))
      (node (ref "U18") (pin "3") (pinfunction "GND_3") (pintype "power_in"))
      (node (ref "U19") (pin "3") (pinfunction "GND_3") (pintype "power_in"))
      (node (ref "U2") (pin "3") (pinfunction "GND_3") (pintype "power_in"))
      (node (ref "U20") (pin "3") (pinfunction "GND_3") (pintype "power_in"))
      (node (ref "U21") (pin "3") (pinfunction "GND_3") (pintype "power_in"))
      (node (ref "U22") (pin "3") (pinfunction "GND_3") (pintype "power_in"))
      (node (ref "U23") (pin "3") (pinfunction "GND_3") (pintype "power_in"))
      (node (ref "U24") (pin "3") (pinfunction "GND_3") (pintype "power_in"))
      (node (ref "U25") (pin "3") (pinfunction "GND_3") (pintype "power_in"))
      (node (ref "U26") (pin "3") (pinfunction "GND_3") (pintype "power_in"))
      (node (ref "U27") (pin "3") (pinfunction "GND_3") (pintype "power_in"))
      (node (ref "U28") (pin "3") (pinfunction "GND_3") (pintype "power_in"))
      (node (ref "U29") (pin "3") (pinfunction "GND_3") (pintype "power_in"))
      (node (ref "U3") (pin "3") (pinfunction "GND_3") (pintype "power_in"))
      (node (ref "U30") (pin "3") (pinfunction "GND_3") (pintype "power_in"))
      (node (ref "U31") (pin "3") (pinfunction "GND_3") (pintype "power_in"))
      (node (ref "U32") (pin "3") (pinfunction "GND_3") (pintype "power_in"))
      (node (ref "U33") (pin "3") (pinfunction "GND_3") (pintype "power_in"))
      (node (ref "U34") (pin "3") (pinfunction "GND_3") (pintype "power_in"))
      (node (ref "U35") (pin "3") (pinfunction "GND_3") (pintype "power_in"))
      (node (ref "U36") (pin "3") (pinfunction "GND_3") (pintype "power_in"))
      (node (ref "U37") (pin "3") (pinfunction "GND_3") (pintype "power_in"))
      (node (ref "U38") (pin "3") (pinfunction "GND_3") (pintype "power_in"))
      (node (ref "U39") (pin "3") (pinfunction "GND_3") (pintype "power_in"))
      (node (ref "U4") (pin "3") (pinfunction "GND_3") (pintype "power_in"))
      (node (ref "U40") (pin "3") (pinfunction "GND_3") (pintype "power_in"))
      (node (ref "U41") (pin "3") (pinfunction "GND_3") (pintype "power_in"))
      (node (ref "U42") (pin "3") (pinfunction "GND_3") (pintype "power_in"))
      (node (ref "U43") (pin "3") (pinfunction "GND_3") (pintype "power_in"))
      (node (ref "U44") (pin "3") (pinfunction "GND_3") (pintype "power_in"))
      (node (ref "U45") (pin "3") (pinfunction "GND_3") (pintype "power_in"))
      (node (ref "U46") (pin "3") (pinfunction "GND_3") (pintype "power_in"))
      (node (ref "U47") (pin "3") (pinfunction "GND_3") (pintype "power_in"))
      (node (ref "U48") (pin "3") (pinfunction "GND_3") (pintype "power_in"))
      (node (ref "U49") (pin "3") (pinfunction "GND_3") (pintype "power_in"))
      (node (ref "U5") (pin "3") (pinfunction "GND_3") (pintype "power_in"))
      (node (ref "U50") (pin "3") (pinfunction "GND_3") (pintype "power_in"))
      (node (ref "U51") (pin "3") (pinfunction "GND_3") (pintype "power_in"))
      (node (ref "U52") (pin "3") (pinfunction "GND_3") (pintype "power_in"))
      (node (ref "U53") (pin "3") (pinfunction "GND_3") (pintype "power_in"))
      (node (ref "U54") (pin "3") (pinfunction "GND_3") (pintype "power_in"))
      (node (ref "U55") (pin "3") (pinfunction "GND_3") (pintype "power_in"))
      (node (ref "U56") (pin "3") (pinfunction "GND_3") (pintype "power_in"))
      (node (ref "U57") (pin "3") (pinfunction "GND_3") (pintype "power_in"))
      (node (ref "U58") (pin "3") (pinfunction "GND_3") (pintype "power_in"))
      (node (ref "U59") (pin "3") (pinfunction "GND_3") (pintype "power_in"))
      (node (ref "U6") (pin "3") (pinfunction "GND_3") (pintype "power_in"))
      (node (ref "U60") (pin "3") (pinfunction "GND_3") (pintype "power_in"))
      (node (ref "U61") (pin "3") (pinfunction "GND_3") (pintype "power_in"))
      (node (ref "U62") (pin "3") (pinfunction "GND_3") (pintype "power_in"))
      (node (ref "U63") (pin "3") (pinfunction "GND_3") (pintype "power_in"))
      (node (ref "U64") (pin "3") (pinfunction "GND_3") (pintype "power_in"))
      (node (ref "U7") (pin "3") (pinfunction "GND_3") (pintype "power_in"))
      (node (ref "U8") (pin "3") (pinfunction "GND_3") (pintype "power_in"))
      (node (ref "U9") (pin "3") (pinfunction "GND_3") (pintype "power_in"))
      (node (ref "X1") (pin "10") (pinfunction "1_10") (pintype "passive"))
      (node (ref "X1") (pin "9") (pinfunction "1_9") (pintype "passive"))
    )
    (net (code "10") (name "Net-(U1-OUT)") (class "Default")
      (node (ref "U1") (pin "2") (pinfunction "OUT_2") (pintype "output"))
      (node (ref "U128") (pin "1") (pinfunction "Y_1") (pintype "bidirectional"))
    )
    (net (code "11") (name "Net-(U10-OUT)") (class "Default")
      (node (ref "U10") (pin "2") (pinfunction "OUT_2") (pintype "output"))
      (node (ref "U119") (pin "1") (pinfunction "Y_1") (pintype "bidirectional"))
    )
    (net (code "12") (name "Net-(U11-OUT)") (class "Default")
      (node (ref "U11") (pin "2") (pinfunction "OUT_2") (pintype "output"))
      (node (ref "U118") (pin "1") (pinfunction "Y_1") (pintype "bidirectional"))
    )
    (net (code "13") (name "Net-(U30-OUT)") (class "Default")
      (node (ref "U30") (pin "2") (pinfunction "OUT_2") (pintype "output"))
      (node (ref "U99") (pin "1") (pinfunction "Y_1") (pintype "bidirectional"))
    )
    (net (code "14") (name "Net-(U31-OUT)") (class "Default")
      (node (ref "U31") (pin "2") (pinfunction "OUT_2") (pintype "output"))
      (node (ref "U98") (pin "1") (pinfunction "Y_1") (pintype "bidirectional"))
    )
    (net (code "15") (name "Net-(U32-OUT)") (class "Default")
      (node (ref "U32") (pin "2") (pinfunction "OUT_2") (pintype "output"))
      (node (ref "U97") (pin "1") (pinfunction "Y_1") (pintype "bidirectional"))
    )
    (net (code "16") (name "Net-(U33-OUT)") (class "Default")
      (node (ref "U33") (pin "2") (pinfunction "OUT_2") (pintype "output"))
      (node (ref "U96") (pin "1") (pinfunction "Y_1") (pintype "bidirectional"))
    )
    (net (code "17") (name "Net-(U34-OUT)") (class "Default")
      (node (ref "U34") (pin "2") (pinfunction "OUT_2") (pintype "output"))
      (node (ref "U95") (pin "1") (pinfunction "Y_1") (pintype "bidirectional"))
    )
    (net (code "18") (name "Net-(U35-OUT)") (class "Default")
      (node (ref "U35") (pin "2") (pinfunction "OUT_2") (pintype "output"))
      (node (ref "U94") (pin "1") (pinfunction "Y_1") (pintype "bidirectional"))
    )
    (net (code "19") (name "Net-(U36-OUT)") (class "Default")
      (node (ref "U36") (pin "2") (pinfunction "OUT_2") (pintype "output"))
      (node (ref "U93") (pin "1") (pinfunction "Y_1") (pintype "bidirectional"))
    )
    (net (code "20") (name "Net-(U37-OUT)") (class "Default")
      (node (ref "U37") (pin "2") (pinfunction "OUT_2") (pintype "output"))
      (node (ref "U92") (pin "1") (pinfunction "Y_1") (pintype "bidirectional"))
    )
    (net (code "21") (name "Net-(U38-OUT)") (class "Default")
      (node (ref "U38") (pin "2") (pinfunction "OUT_2") (pintype "output"))
      (node (ref "U91") (pin "1") (pinfunction "Y_1") (pintype "bidirectional"))
    )
    (net (code "22") (name "Net-(U39-OUT)") (class "Default")
      (node (ref "U39") (pin "2") (pinfunction "OUT_2") (pintype "output"))
      (node (ref "U90") (pin "1") (pinfunction "Y_1") (pintype "bidirectional"))
    )
    (net (code "23") (name "Net-(U40-OUT)") (class "Default")
      (node (ref "U40") (pin "2") (pinfunction "OUT_2") (pintype "output"))
      (node (ref "U89") (pin "1") (pinfunction "Y_1") (pintype "bidirectional"))
    )
    (net (code "24") (name "Net-(U41-OUT)") (class "Default")
      (node (ref "U41") (pin "2") (pinfunction "OUT_2") (pintype "output"))
      (node (ref "U88") (pin "1") (pinfunction "Y_1") (pintype "bidirectional"))
    )
    (net (code "25") (name "Net-(U42-OUT)") (class "Default")
      (node (ref "U42") (pin "2") (pinfunction "OUT_2") (pintype "output"))
      (node (ref "U87") (pin "1") (pinfunction "Y_1") (pintype "bidirectional"))
    )
    (net (code "26") (name "Net-(U43-OUT)") (class "Default")
      (node (ref "U43") (pin "2") (pinfunction "OUT_2") (pintype "output"))
      (node (ref "U86") (pin "1") (pinfunction "Y_1") (pintype "bidirectional"))
    )
    (net (code "27") (name "Net-(U44-OUT)") (class "Default")
      (node (ref "U44") (pin "2") (pinfunction "OUT_2") (pintype "output"))
      (node (ref "U85") (pin "1") (pinfunction "Y_1") (pintype "bidirectional"))
    )
    (net (code "28") (name "Net-(U45-OUT)") (class "Default")
      (node (ref "U45") (pin "2") (pinfunction "OUT_2") (pintype "output"))
      (node (ref "U84") (pin "1") (pinfunction "Y_1") (pintype "bidirectional"))
    )
    (net (code "29") (name "Net-(U46-OUT)") (class "Default")
      (node (ref "U46") (pin "2") (pinfunction "OUT_2") (pintype "output"))
      (node (ref "U83") (pin "1") (pinfunction "Y_1") (pintype "bidirectional"))
    )
    (net (code "30") (name "Net-(U47-OUT)") (class "Default")
      (node (ref "U47") (pin "2") (pinfunction "OUT_2") (pintype "output"))
      (node (ref "U82") (pin "1") (pinfunction "Y_1") (pintype "bidirectional"))
    )
    (net (code "31") (name "Net-(U48-OUT)") (class "Default")
      (node (ref "U48") (pin "2") (pinfunction "OUT_2") (pintype "output"))
      (node (ref "U81") (pin "1") (pinfunction "Y_1") (pintype "bidirectional"))
    )
    (net (code "32") (name "Net-(U49-OUT)") (class "Default")
      (node (ref "U49") (pin "2") (pinfunction "OUT_2") (pintype "output"))
      (node (ref "U80") (pin "1") (pinfunction "Y_1") (pintype "bidirectional"))
    )
    (net (code "33") (name "Net-(U50-OUT)") (class "Default")
      (node (ref "U50") (pin "2") (pinfunction "OUT_2") (pintype "output"))
      (node (ref "U79") (pin "1") (pinfunction "Y_1") (pintype "bidirectional"))
    )
    (net (code "34") (name "Net-(U51-OUT)") (class "Default")
      (node (ref "U51") (pin "2") (pinfunction "OUT_2") (pintype "output"))
      (node (ref "U78") (pin "1") (pinfunction "Y_1") (pintype "bidirectional"))
    )
    (net (code "35") (name "Net-(U52-OUT)") (class "Default")
      (node (ref "U52") (pin "2") (pinfunction "OUT_2") (pintype "output"))
      (node (ref "U77") (pin "1") (pinfunction "Y_1") (pintype "bidirectional"))
    )
    (net (code "36") (name "Net-(U53-OUT)") (class "Default")
      (node (ref "U53") (pin "2") (pinfunction "OUT_2") (pintype "output"))
      (node (ref "U76") (pin "1") (pinfunction "Y_1") (pintype "bidirectional"))
    )
    (net (code "37") (name "Net-(U54-OUT)") (class "Default")
      (node (ref "U54") (pin "2") (pinfunction "OUT_2") (pintype "output"))
      (node (ref "U75") (pin "1") (pinfunction "Y_1") (pintype "bidirectional"))
    )
    (net (code "38") (name "Net-(U55-OUT)") (class "Default")
      (node (ref "U55") (pin "2") (pinfunction "OUT_2") (pintype "output"))
      (node (ref "U74") (pin "1") (pinfunction "Y_1") (pintype "bidirectional"))
    )
    (net (code "39") (name "Net-(U56-OUT)") (class "Default")
      (node (ref "U56") (pin "2") (pinfunction "OUT_2") (pintype "output"))
      (node (ref "U73") (pin "1") (pinfunction "Y_1") (pintype "bidirectional"))
    )
    (net (code "40") (name "Net-(U57-OUT)") (class "Default")
      (node (ref "U57") (pin "2") (pinfunction "OUT_2") (pintype "output"))
      (node (ref "U72") (pin "1") (pinfunction "Y_1") (pintype "bidirectional"))
    )
    (net (code "41") (name "Net-(U58-OUT)") (class "Default")
      (node (ref "U58") (pin "2") (pinfunction "OUT_2") (pintype "output"))
      (node (ref "U71") (pin "1") (pinfunction "Y_1") (pintype "bidirectional"))
    )
    (net (code "42") (name "Net-(U59-OUT)") (class "Default")
      (node (ref "U59") (pin "2") (pinfunction "OUT_2") (pintype "output"))
      (node (ref "U70") (pin "1") (pinfunction "Y_1") (pintype "bidirectional"))
    )
    (net (code "43") (name "Net-(U60-OUT)") (class "Default")
      (node (ref "U60") (pin "2") (pinfunction "OUT_2") (pintype "output"))
      (node (ref "U69") (pin "1") (pinfunction "Y_1") (pintype "bidirectional"))
    )
    (net (code "44") (name "Net-(U61-OUT)") (class "Default")
      (node (ref "U61") (pin "2") (pinfunction "OUT_2") (pintype "output"))
      (node (ref "U68") (pin "1") (pinfunction "Y_1") (pintype "bidirectional"))
    )
    (net (code "45") (name "Net-(U62-OUT)") (class "Default")
      (node (ref "U62") (pin "2") (pinfunction "OUT_2") (pintype "output"))
      (node (ref "U67") (pin "1") (pinfunction "Y_1") (pintype "bidirectional"))
    )
    (net (code "46") (name "Net-(U63-OUT)") (class "Default")
      (node (ref "U63") (pin "2") (pinfunction "OUT_2") (pintype "output"))
      (node (ref "U66") (pin "1") (pinfunction "Y_1") (pintype "bidirectional"))
    )
    (net (code "47") (name "Net-(U64-OUT)") (class "Default")
      (node (ref "U64") (pin "2") (pinfunction "OUT_2") (pintype "output"))
      (node (ref "U65") (pin "1") (pinfunction "Y_1") (pintype "bidirectional"))
    )
    (net (code "48") (name "Net-(U100A-Y)") (class "Default")
      (node (ref "U100") (pin "1") (pinfunction "Y_1") (pintype "bidirectional"))
      (node (ref "U29") (pin "2") (pinfunction "OUT_2") (pintype "output"))
    )
    (net (code "49") (name "Net-(U101A-Y)") (class "Default")
      (node (ref "U101") (pin "1") (pinfunction "Y_1") (pintype "bidirectional"))
      (node (ref "U28") (pin "2") (pinfunction "OUT_2") (pintype "output"))
    )
    (net (code "50") (name "Net-(U102A-Y)") (class "Default")
      (node (ref "U102") (pin "1") (pinfunction "Y_1") (pintype "bidirectional"))
      (node (ref "U27") (pin "2") (pinfunction "OUT_2") (pintype "output"))
    )
    (net (code "51") (name "Net-(U103A-Y)") (class "Default")
      (node (ref "U103") (pin "1") (pinfunction "Y_1") (pintype "bidirectional"))
      (node (ref "U26") (pin "2") (pinfunction "OUT_2") (pintype "output"))
    )
    (net (code "52") (name "Net-(U104A-Y)") (class "Default")
      (node (ref "U104") (pin "1") (pinfunction "Y_1") (pintype "bidirectional"))
      (node (ref "U25") (pin "2") (pinfunction "OUT_2") (pintype "output"))
    )
    (net (code "53") (name "Net-(U105A-Y)") (class "Default")
      (node (ref "U105") (pin "1") (pinfunction "Y_1") (pintype "bidirectional"))
      (node (ref "U24") (pin "2") (pinfunction "OUT_2") (pintype "output"))
    )
    (net (code "54") (name "Net-(U106A-Y)") (class "Default")
      (node (ref "U106") (pin "1") (pinfunction "Y_1") (pintype "bidirectional"))
      (node (ref "U23") (pin "2") (pinfunction "OUT_2") (pintype "output"))
    )
    (net (code "55") (name "Net-(U107A-Y)") (class "Default")
      (node (ref "U107") (pin "1") (pinfunction "Y_1") (pintype "bidirectional"))
      (node (ref "U22") (pin "2") (pinfunction "OUT_2") (pintype "output"))
    )
    (net (code "56") (name "Net-(U108A-Y)") (class "Default")
      (node (ref "U108") (pin "1") (pinfunction "Y_1") (pintype "bidirectional"))
      (node (ref "U21") (pin "2") (pinfunction "OUT_2") (pintype "output"))
    )
    (net (code "57") (name "Net-(U109A-Y)") (class "Default")
      (node (ref "U109") (pin "1") (pinfunction "Y_1") (pintype "bidirectional"))
      (node (ref "U20") (pin "2") (pinfunction "OUT_2") (pintype "output"))
    )
    (net (code "58") (name "Net-(U110A-Y)") (class "Default")
      (node (ref "U110") (pin "1") (pinfunction "Y_1") (pintype "bidirectional"))
      (node (ref "U19") (pin "2") (pinfunction "OUT_2") (pintype "output"))
    )
    (net (code "59") (name "Net-(U111A-Y)") (class "Default")
      (node (ref "U111") (pin "1") (pinfunction "Y_1") (pintype "bidirectional"))
      (node (ref "U18") (pin "2") (pinfunction "OUT_2") (pintype "output"))
    )
    (net (code "60") (name "Net-(U112A-Y)") (class "Default")
      (node (ref "U112") (pin "1") (pinfunction "Y_1") (pintype "bidirectional"))
      (node (ref "U17") (pin "2") (pinfunction "OUT_2") (pintype "output"))
    )
    (net (code "61") (name "Net-(U113A-Y)") (class "Default")
      (node (ref "U113") (pin "1") (pinfunction "Y_1") (pintype "bidirectional"))
      (node (ref "U16") (pin "2") (pinfunction "OUT_2") (pintype "output"))
    )
    (net (code "62") (name "Net-(U114A-Y)") (class "Default")
      (node (ref "U114") (pin "1") (pinfunction "Y_1") (pintype "bidirectional"))
      (node (ref "U15") (pin "2") (pinfunction "OUT_2") (pintype "output"))
    )
    (net (code "63") (name "Net-(U115A-Y)") (class "Default")
      (node (ref "U115") (pin "1") (pinfunction "Y_1") (pintype "bidirectional"))
      (node (ref "U14") (pin "2") (pinfunction "OUT_2") (pintype "output"))
    )
    (net (code "64") (name "Net-(U116A-Y)") (class "Default")
      (node (ref "U116") (pin "1") (pinfunction "Y_1") (pintype "bidirectional"))
      (node (ref "U13") (pin "2") (pinfunction "OUT_2") (pintype "output"))
    )
    (net (code "65") (name "Net-(U117A-Y)") (class "Default")
      (node (ref "U117") (pin "1") (pinfunction "Y_1") (pintype "bidirectional"))
      (node (ref "U12") (pin "2") (pinfunction "OUT_2") (pintype "output"))
    )
    (net (code "66") (name "Net-(U120A-Y)") (class "Default")
      (node (ref "U120") (pin "1") (pinfunction "Y_1") (pintype "bidirectional"))
      (node (ref "U9") (pin "2") (pinfunction "OUT_2") (pintype "output"))
    )
    (net (code "67") (name "Net-(U121A-Y)") (class "Default")
      (node (ref "U121") (pin "1") (pinfunction "Y_1") (pintype "bidirectional"))
      (node (ref "U8") (pin "2") (pinfunction "OUT_2") (pintype "output"))
    )
    (net (code "68") (name "Net-(U122A-Y)") (class "Default")
      (node (ref "U122") (pin "1") (pinfunction "Y_1") (pintype "bidirectional"))
      (node (ref "U7") (pin "2") (pinfunction "OUT_2") (pintype "output"))
    )
    (net (code "69") (name "Net-(U123A-Y)") (class "Default")
      (node (ref "U123") (pin "1") (pinfunction "Y_1") (pintype "bidirectional"))
      (node (ref "U6") (pin "2") (pinfunction "OUT_2") (pintype "output"))
    )
    (net (code "70") (name "Net-(U124A-Y)") (class "Default")
      (node (ref "U124") (pin "1") (pinfunction "Y_1") (pintype "bidirectional"))
      (node (ref "U5") (pin "2") (pinfunction "OUT_2") (pintype "output"))
    )
    (net (code "71") (name "Net-(U125A-Y)") (class "Default")
      (node (ref "U125") (pin "1") (pinfunction "Y_1") (pintype "bidirectional"))
      (node (ref "U4") (pin "2") (pinfunction "OUT_2") (pintype "output"))
    )
    (net (code "72") (name "Net-(U126A-Y)") (class "Default")
      (node (ref "U126") (pin "1") (pinfunction "Y_1") (pintype "bidirectional"))
      (node (ref "U3") (pin "2") (pinfunction "OUT_2") (pintype "output"))
    )
    (net (code "73") (name "Net-(U127A-Y)") (class "Default")
      (node (ref "U127") (pin "1") (pinfunction "Y_1") (pintype "bidirectional"))
      (node (ref "U2") (pin "2") (pinfunction "OUT_2") (pintype "output"))
    )
    (net (code "74") (name "ROW0") (class "Default")
      (node (ref "U121") (pin "2") (pinfunction "Z_2") (pintype "bidirectional"))
      (node (ref "U122") (pin "2") (pinfunction "Z_2") (pintype "bidirectional"))
      (node (ref "U123") (pin "2") (pinfunction "Z_2") (pintype "bidirectional"))
      (node (ref "U124") (pin "2") (pinfunction "Z_2") (pintype "bidirectional"))
      (node (ref "U125") (pin "2") (pinfunction "Z_2") (pintype "bidirectional"))
      (node (ref "U126") (pin "2") (pinfunction "Z_2") (pintype "bidirectional"))
      (node (ref "U127") (pin "2") (pinfunction "Z_2") (pintype "bidirectional"))
      (node (ref "U128") (pin "2") (pinfunction "Z_2") (pintype "bidirectional"))
      (node (ref "X1") (pin "1") (pinfunction "1_1") (pintype "passive"))
    )
    (net (code "75") (name "ROW1") (class "Default")
      (node (ref "U113") (pin "2") (pinfunction "Z_2") (pintype "bidirectional"))
      (node (ref "U114") (pin "2") (pinfunction "Z_2") (pintype "bidirectional"))
      (node (ref "U115") (pin "2") (pinfunction "Z_2") (pintype "bidirectional"))
      (node (ref "U116") (pin "2") (pinfunction "Z_2") (pintype "bidirectional"))
      (node (ref "U117") (pin "2") (pinfunction "Z_2") (pintype "bidirectional"))
      (node (ref "U118") (pin "2") (pinfunction "Z_2") (pintype "bidirectional"))
      (node (ref "U119") (pin "2") (pinfunction "Z_2") (pintype "bidirectional"))
      (node (ref "U120") (pin "2") (pinfunction "Z_2") (pintype "bidirectional"))
      (node (ref "X1") (pin "2") (pinfunction "1_2") (pintype "passive"))
    )
    (net (code "76") (name "ROW2") (class "Default")
      (node (ref "U105") (pin "2") (pinfunction "Z_2") (pintype "bidirectional"))
      (node (ref "U106") (pin "2") (pinfunction "Z_2") (pintype "bidirectional"))
      (node (ref "U107") (pin "2") (pinfunction "Z_2") (pintype "bidirectional"))
      (node (ref "U108") (pin "2") (pinfunction "Z_2") (pintype "bidirectional"))
      (node (ref "U109") (pin "2") (pinfunction "Z_2") (pintype "bidirectional"))
      (node (ref "U110") (pin "2") (pinfunction "Z_2") (pintype "bidirectional"))
      (node (ref "U111") (pin "2") (pinfunction "Z_2") (pintype "bidirectional"))
      (node (ref "U112") (pin "2") (pinfunction "Z_2") (pintype "bidirectional"))
      (node (ref "X1") (pin "3") (pinfunction "1_3") (pintype "passive"))
    )
    (net (code "77") (name "ROW3") (class "Default")
      (node (ref "U100") (pin "2") (pinfunction "Z_2") (pintype "bidirectional"))
      (node (ref "U101") (pin "2") (pinfunction "Z_2") (pintype "bidirectional"))
      (node (ref "U102") (pin "2") (pinfunction "Z_2") (pintype "bidirectional"))
      (node (ref "U103") (pin "2") (pinfunction "Z_2") (pintype "bidirectional"))
      (node (ref "U104") (pin "2") (pinfunction "Z_2") (pintype "bidirectional"))
      (node (ref "U97") (pin "2") (pinfunction "Z_2") (pintype "bidirectional"))
      (node (ref "U98") (pin "2") (pinfunction "Z_2") (pintype "bidirectional"))
      (node (ref "U99") (pin "2") (pinfunction "Z_2") (pintype "bidirectional"))
      (node (ref "X1") (pin "4") (pinfunction "1_4") (pintype "passive"))
    )
    (net (code "78") (name "ROW4") (class "Default")
      (node (ref "U89") (pin "2") (pinfunction "Z_2") (pintype "bidirectional"))
      (node (ref "U90") (pin "2") (pinfunction "Z_2") (pintype "bidirectional"))
      (node (ref "U91") (pin "2") (pinfunction "Z_2") (pintype "bidirectional"))
      (node (ref "U92") (pin "2") (pinfunction "Z_2") (pintype "bidirectional"))
      (node (ref "U93") (pin "2") (pinfunction "Z_2") (pintype "bidirectional"))
      (node (ref "U94") (pin "2") (pinfunction "Z_2") (pintype "bidirectional"))
      (node (ref "U95") (pin "2") (pinfunction "Z_2") (pintype "bidirectional"))
      (node (ref "U96") (pin "2") (pinfunction "Z_2") (pintype "bidirectional"))
      (node (ref "X1") (pin "5") (pinfunction "1_5") (pintype "passive"))
    )
    (net (code "79") (name "ROW5") (class "Default")
      (node (ref "U81") (pin "2") (pinfunction "Z_2") (pintype "bidirectional"))
      (node (ref "U82") (pin "2") (pinfunction "Z_2") (pintype "bidirectional"))
      (node (ref "U83") (pin "2") (pinfunction "Z_2") (pintype "bidirectional"))
      (node (ref "U84") (pin "2") (pinfunction "Z_2") (pintype "bidirectional"))
      (node (ref "U85") (pin "2") (pinfunction "Z_2") (pintype "bidirectional"))
      (node (ref "U86") (pin "2") (pinfunction "Z_2") (pintype "bidirectional"))
      (node (ref "U87") (pin "2") (pinfunction "Z_2") (pintype "bidirectional"))
      (node (ref "U88") (pin "2") (pinfunction "Z_2") (pintype "bidirectional"))
      (node (ref "X1") (pin "6") (pinfunction "1_6") (pintype "passive"))
    )
    (net (code "80") (name "ROW6") (class "Default")
      (node (ref "U73") (pin "2") (pinfunction "Z_2") (pintype "bidirectional"))
      (node (ref "U74") (pin "2") (pinfunction "Z_2") (pintype "bidirectional"))
      (node (ref "U75") (pin "2") (pinfunction "Z_2") (pintype "bidirectional"))
      (node (ref "U76") (pin "2") (pinfunction "Z_2") (pintype "bidirectional"))
      (node (ref "U77") (pin "2") (pinfunction "Z_2") (pintype "bidirectional"))
      (node (ref "U78") (pin "2") (pinfunction "Z_2") (pintype "bidirectional"))
      (node (ref "U79") (pin "2") (pinfunction "Z_2") (pintype "bidirectional"))
      (node (ref "U80") (pin "2") (pinfunction "Z_2") (pintype "bidirectional"))
      (node (ref "X1") (pin "7") (pinfunction "1_7") (pintype "passive"))
    )
    (net (code "81") (name "ROW7") (class "Default")
      (node (ref "U65") (pin "2") (pinfunction "Z_2") (pintype "bidirectional"))
      (node (ref "U66") (pin "2") (pinfunction "Z_2") (pintype "bidirectional"))
      (node (ref "U67") (pin "2") (pinfunction "Z_2") (pintype "bidirectional"))
      (node (ref "U68") (pin "2") (pinfunction "Z_2") (pintype "bidirectional"))
      (node (ref "U69") (pin "2") (pinfunction "Z_2") (pintype "bidirectional"))
      (node (ref "U70") (pin "2") (pinfunction "Z_2") (pintype "bidirectional"))
      (node (ref "U71") (pin "2") (pinfunction "Z_2") (pintype "bidirectional"))
      (node (ref "U72") (pin "2") (pinfunction "Z_2") (pintype "bidirectional"))
      (node (ref "X1") (pin "8") (pinfunction "1_8") (pintype "passive"))
    )
    (net (code "82") (name "VCC") (class "Default")
      (node (ref "C1") (pin "1") (pinfunction "1_1") (pintype "passive"))
      (node (ref "C10") (pin "1") (pinfunction "1_1") (pintype "passive"))
      (node (ref "C11") (pin "1") (pinfunction "1_1") (pintype "passive"))
      (node (ref "C12") (pin "1") (pinfunction "1_1") (pintype "passive"))
      (node (ref "C13") (pin "1") (pinfunction "1_1") (pintype "passive"))
      (node (ref "C14") (pin "1") (pinfunction "1_1") (pintype "passive"))
      (node (ref "C15") (pin "1") (pinfunction "1_1") (pintype "passive"))
      (node (ref "C16") (pin "1") (pinfunction "1_1") (pintype "passive"))
      (node (ref "C17") (pin "1") (pinfunction "1_1") (pintype "passive"))
      (node (ref "C18") (pin "1") (pinfunction "1_1") (pintype "passive"))
      (node (ref "C19") (pin "1") (pinfunction "1_1") (pintype "passive"))
      (node (ref "C2") (pin "1") (pinfunction "1_1") (pintype "passive"))
      (node (ref "C20") (pin "1") (pinfunction "1_1") (pintype "passive"))
      (node (ref "C21") (pin "1") (pinfunction "1_1") (pintype "passive"))
      (node (ref "C22") (pin "1") (pinfunction "1_1") (pintype "passive"))
      (node (ref "C23") (pin "1") (pinfunction "1_1") (pintype "passive"))
      (node (ref "C24") (pin "1") (pinfunction "1_1") (pintype "passive"))
      (node (ref "C25") (pin "1") (pinfunction "1_1") (pintype "passive"))
      (node (ref "C26") (pin "1") (pinfunction "1_1") (pintype "passive"))
      (node (ref "C27") (pin "1") (pinfunction "1_1") (pintype "passive"))
      (node (ref "C28") (pin "1") (pinfunction "1_1") (pintype "passive"))
      (node (ref "C29") (pin "1") (pinfunction "1_1") (pintype "passive"))
      (node (ref "C3") (pin "1") (pinfunction "1_1") (pintype "passive"))
      (node (ref "C30") (pin "1") (pinfunction "1_1") (pintype "passive"))
      (node (ref "C31") (pin "1") (pinfunction "1_1") (pintype "passive"))
      (node (ref "C32") (pin "1") (pinfunction "1_1") (pintype "passive"))
      (node (ref "C33") (pin "1") (pinfunction "1_1") (pintype "passive"))
      (node (ref "C34") (pin "1") (pinfunction "1_1") (pintype "passive"))
      (node (ref "C35") (pin "1") (pinfunction "1_1") (pintype "passive"))
      (node (ref "C36") (pin "1") (pinfunction "1_1") (pintype "passive"))
      (node (ref "C37") (pin "1") (pinfunction "1_1") (pintype "passive"))
      (node (ref "C38") (pin "1") (pinfunction "1_1") (pintype "passive"))
      (node (ref "C39") (pin "1") (pinfunction "1_1") (pintype "passive"))
      (node (ref "C4") (pin "1") (pinfunction "1_1") (pintype "passive"))
      (node (ref "C40") (pin "1") (pinfunction "1_1") (pintype "passive"))
      (node (ref "C41") (pin "1") (pinfunction "1_1") (pintype "passive"))
      (node (ref "C42") (pin "1") (pinfunction "1_1") (pintype "passive"))
      (node (ref "C43") (pin "1") (pinfunction "1_1") (pintype "passive"))
      (node (ref "C44") (pin "1") (pinfunction "1_1") (pintype "passive"))
      (node (ref "C45") (pin "1") (pinfunction "1_1") (pintype "passive"))
      (node (ref "C46") (pin "1") (pinfunction "1_1") (pintype "passive"))
      (node (ref "C47") (pin "1") (pinfunction "1_1") (pintype "passive"))
      (node (ref "C48") (pin "1") (pinfunction "1_1") (pintype "passive"))
      (node (ref "C49") (pin "1") (pinfunction "1_1") (pintype "passive"))
      (node (ref "C5") (pin "1") (pinfunction "1_1") (pintype "passive"))
      (node (ref "C50") (pin "1") (pinfunction "1_1") (pintype "passive"))
      (node (ref "C51") (pin "1") (pinfunction "1_1") (pintype "passive"))
      (node (ref "C52") (pin "1") (pinfunction "1_1") (pintype "passive"))
      (node (ref "C53") (pin "1") (pinfunction "1_1") (pintype "passive"))
      (node (ref "C54") (pin "1") (pinfunction "1_1") (pintype "passive"))
      (node (ref "C55") (pin "1") (pinfunction "1_1") (pintype "passive"))
      (node (ref "C56") (pin "1") (pinfunction "1_1") (pintype "passive"))
      (node (ref "C6") (pin "1") (pinfunction "1_1") (pintype "passive"))
      (node (ref "C7") (pin "1") (pinfunction "1_1") (pintype "passive"))
      (node (ref "C8") (pin "1") (pinfunction "1_1") (pintype "passive"))
      (node (ref "C9") (pin "1") (pinfunction "1_1") (pintype "passive"))
      (node (ref "U1") (pin "1") (pinfunction "VCC_1") (pintype "power_in"))
      (node (ref "U10") (pin "1") (pinfunction "VCC_1") (pintype "power_in"))
      (node (ref "U11") (pin "1") (pinfunction "VCC_1") (pintype "power_in"))
      (node (ref "U12") (pin "1") (pinfunction "VCC_1") (pintype "power_in"))
      (node (ref "U13") (pin "1") (pinfunction "VCC_1") (pintype "power_in"))
      (node (ref "U14") (pin "1") (pinfunction "VCC_1") (pintype "power_in"))
      (node (ref "U15") (pin "1") (pinfunction "VCC_1") (pintype "power_in"))
      (node (ref "U16") (pin "1") (pinfunction "VCC_1") (pintype "power_in"))
      (node (ref "U17") (pin "1") (pinfunction "VCC_1") (pintype "power_in"))
      (node (ref "U18") (pin "1") (pinfunction "VCC_1") (pintype "power_in"))
      (node (ref "U19") (pin "1") (pinfunction "VCC_1") (pintype "power_in"))
      (node (ref "U2") (pin "1") (pinfunction "VCC_1") (pintype "power_in"))
      (node (ref "U20") (pin "1") (pinfunction "VCC_1") (pintype "power_in"))
      (node (ref "U21") (pin "1") (pinfunction "VCC_1") (pintype "power_in"))
      (node (ref "U22") (pin "1") (pinfunction "VCC_1") (pintype "power_in"))
      (node (ref "U23") (pin "1") (pinfunction "VCC_1") (pintype "power_in"))
      (node (ref "U24") (pin "1") (pinfunction "VCC_1") (pintype "power_in"))
      (node (ref "U25") (pin "1") (pinfunction "VCC_1") (pintype "power_in"))
      (node (ref "U26") (pin "1") (pinfunction "VCC_1") (pintype "power_in"))
      (node (ref "U27") (pin "1") (pinfunction "VCC_1") (pintype "power_in"))
      (node (ref "U28") (pin "1") (pinfunction "VCC_1") (pintype "power_in"))
      (node (ref "U29") (pin "1") (pinfunction "VCC_1") (pintype "power_in"))
      (node (ref "U3") (pin "1") (pinfunction "VCC_1") (pintype "power_in"))
      (node (ref "U30") (pin "1") (pinfunction "VCC_1") (pintype "power_in"))
      (node (ref "U31") (pin "1") (pinfunction "VCC_1") (pintype "power_in"))
      (node (ref "U32") (pin "1") (pinfunction "VCC_1") (pintype "power_in"))
      (node (ref "U33") (pin "1") (pinfunction "VCC_1") (pintype "power_in"))
      (node (ref "U34") (pin "1") (pinfunction "VCC_1") (pintype "power_in"))
      (node (ref "U35") (pin "1") (pinfunction "VCC_1") (pintype "power_in"))
      (node (ref "U36") (pin "1") (pinfunction "VCC_1") (pintype "power_in"))
      (node (ref "U37") (pin "1") (pinfunction "VCC_1") (pintype "power_in"))
      (node (ref "U38") (pin "1") (pinfunction "VCC_1") (pintype "power_in"))
      (node (ref "U39") (pin "1") (pinfunction "VCC_1") (pintype "power_in"))
      (node (ref "U4") (pin "1") (pinfunction "VCC_1") (pintype "power_in"))
      (node (ref "U40") (pin "1") (pinfunction "VCC_1") (pintype "power_in"))
      (node (ref "U41") (pin "1") (pinfunction "VCC_1") (pintype "power_in"))
      (node (ref "U42") (pin "1") (pinfunction "VCC_1") (pintype "power_in"))
      (node (ref "U43") (pin "1") (pinfunction "VCC_1") (pintype "power_in"))
      (node (ref "U44") (pin "1") (pinfunction "VCC_1") (pintype "power_in"))
      (node (ref "U45") (pin "1") (pinfunction "VCC_1") (pintype "power_in"))
      (node (ref "U46") (pin "1") (pinfunction "VCC_1") (pintype "power_in"))
      (node (ref "U47") (pin "1") (pinfunction "VCC_1") (pintype "power_in"))
      (node (ref "U48") (pin "1") (pinfunction "VCC_1") (pintype "power_in"))
      (node (ref "U49") (pin "1") (pinfunction "VCC_1") (pintype "power_in"))
      (node (ref "U5") (pin "1") (pinfunction "VCC_1") (pintype "power_in"))
      (node (ref "U50") (pin "1") (pinfunction "VCC_1") (pintype "power_in"))
      (node (ref "U51") (pin "1") (pinfunction "VCC_1") (pintype "power_in"))
      (node (ref "U52") (pin "1") (pinfunction "VCC_1") (pintype "power_in"))
      (node (ref "U53") (pin "1") (pinfunction "VCC_1") (pintype "power_in"))
      (node (ref "U54") (pin "1") (pinfunction "VCC_1") (pintype "power_in"))
      (node (ref "U55") (pin "1") (pinfunction "VCC_1") (pintype "power_in"))
      (node (ref "U56") (pin "1") (pinfunction "VCC_1") (pintype "power_in"))
      (node (ref "U57") (pin "1") (pinfunction "VCC_1") (pintype "power_in"))
      (node (ref "U58") (pin "1") (pinfunction "VCC_1") (pintype "power_in"))
      (node (ref "U59") (pin "1") (pinfunction "VCC_1") (pintype "power_in"))
      (node (ref "U6") (pin "1") (pinfunction "VCC_1") (pintype "power_in"))
      (node (ref "U60") (pin "1") (pinfunction "VCC_1") (pintype "power_in"))
      (node (ref "U61") (pin "1") (pinfunction "VCC_1") (pintype "power_in"))
      (node (ref "U62") (pin "1") (pinfunction "VCC_1") (pintype "power_in"))
      (node (ref "U63") (pin "1") (pinfunction "VCC_1") (pintype "power_in"))
      (node (ref "U64") (pin "1") (pinfunction "VCC_1") (pintype "power_in"))
      (node (ref "U7") (pin "1") (pinfunction "VCC_1") (pintype "power_in"))
      (node (ref "U8") (pin "1") (pinfunction "VCC_1") (pintype "power_in"))
      (node (ref "U9") (pin "1") (pinfunction "VCC_1") (pintype "power_in"))
      (node (ref "X1") (pin "11") (pinfunction "1_11") (pintype "passive"))
      (node (ref "X1") (pin "12") (pinfunction "1_12") (pintype "passive"))
    )
  )
)
